# A1-A1_Active_Bias.net
KiCad netlist of a schematic drawn in Altium Designer
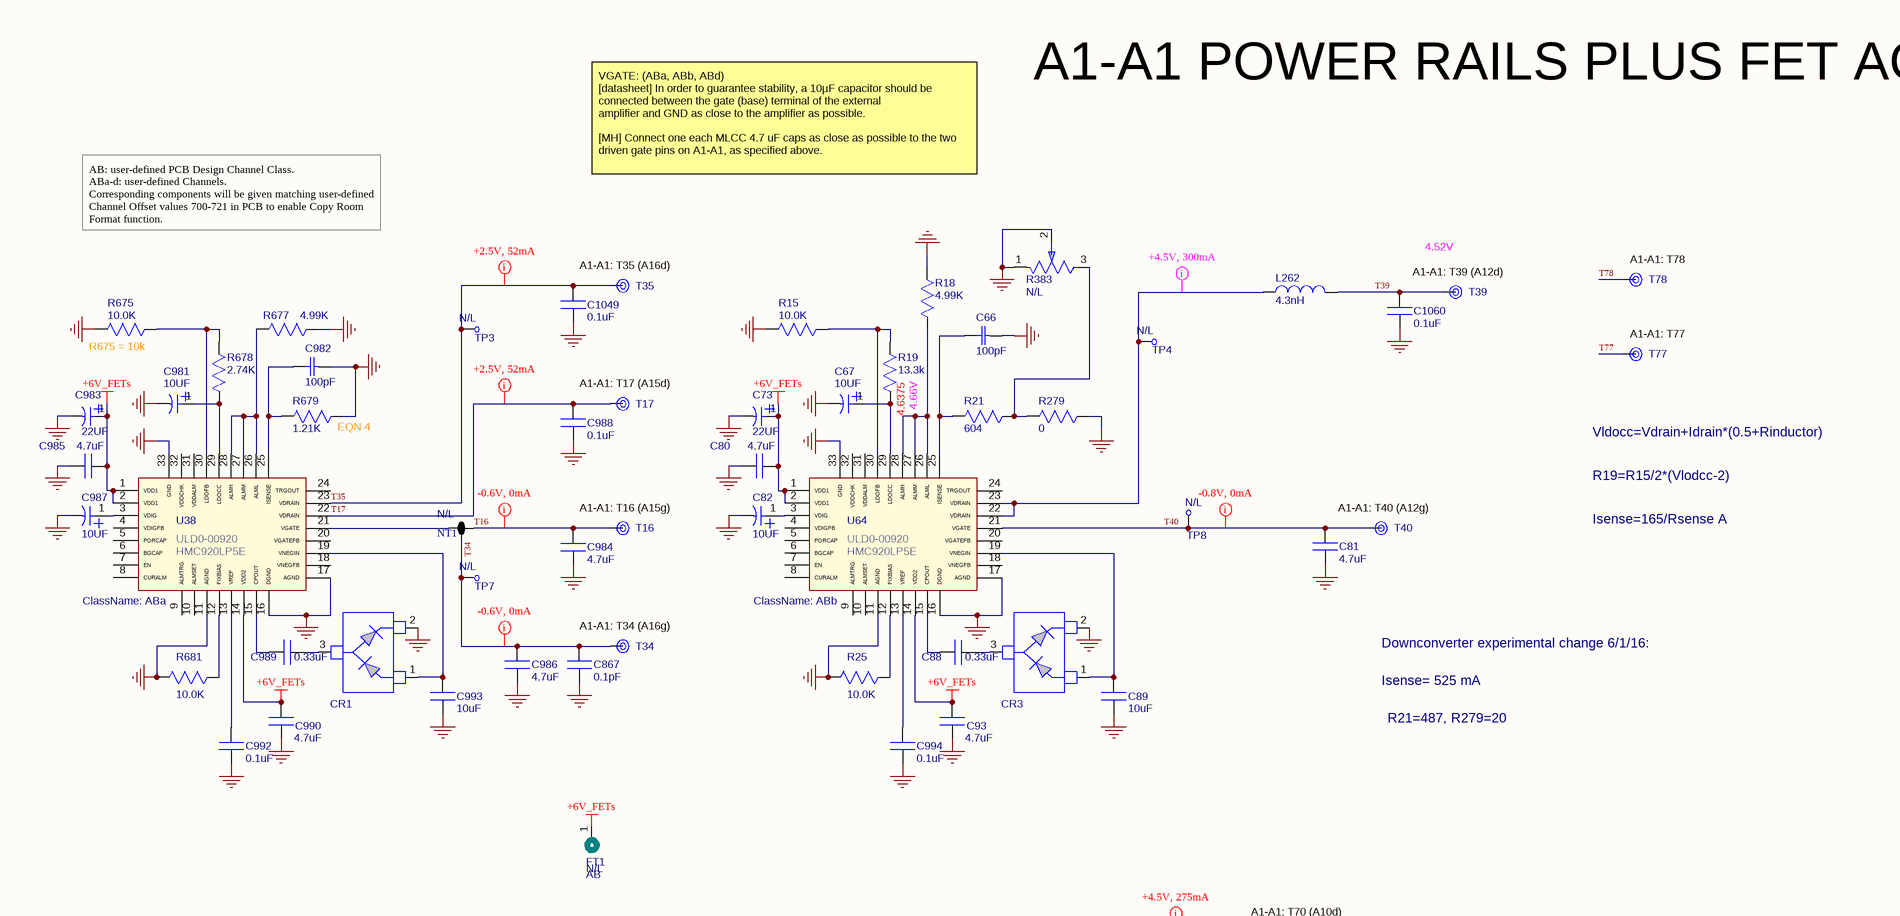
[diagram p0: A1-A1 Active Bias.SchDoc, top left]
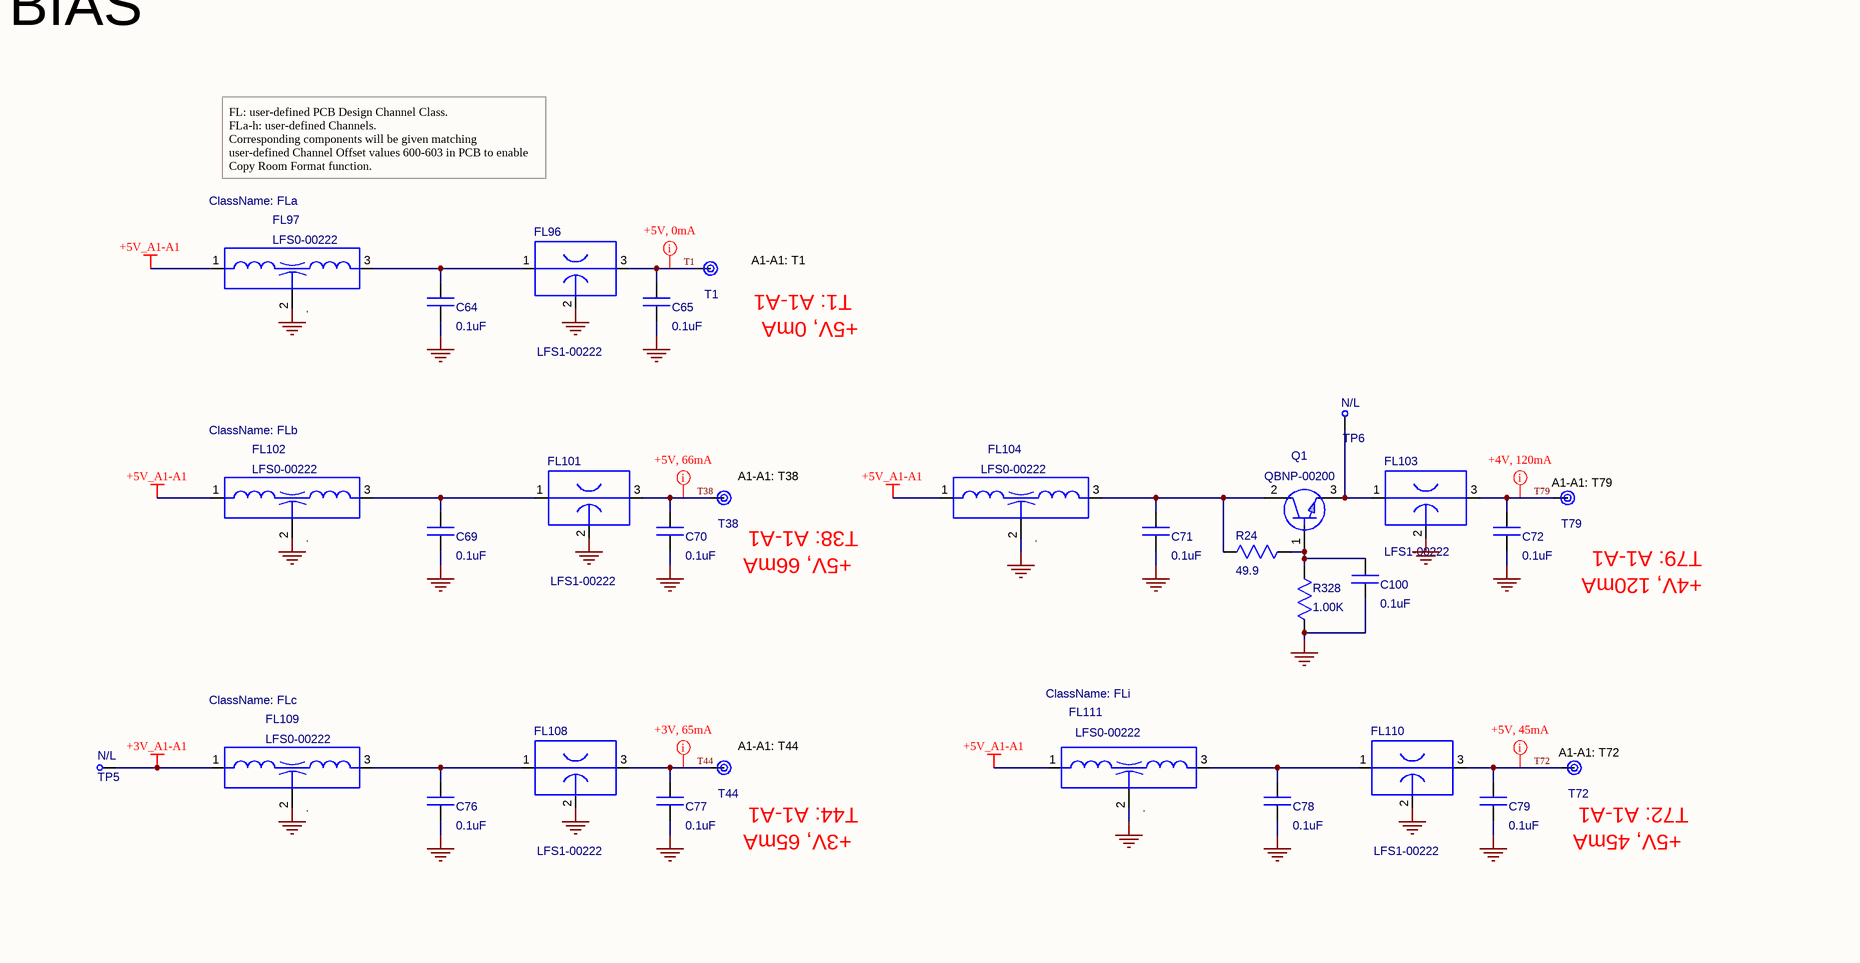
[diagram p1: A1-A1 Active Bias.SchDoc, top right]
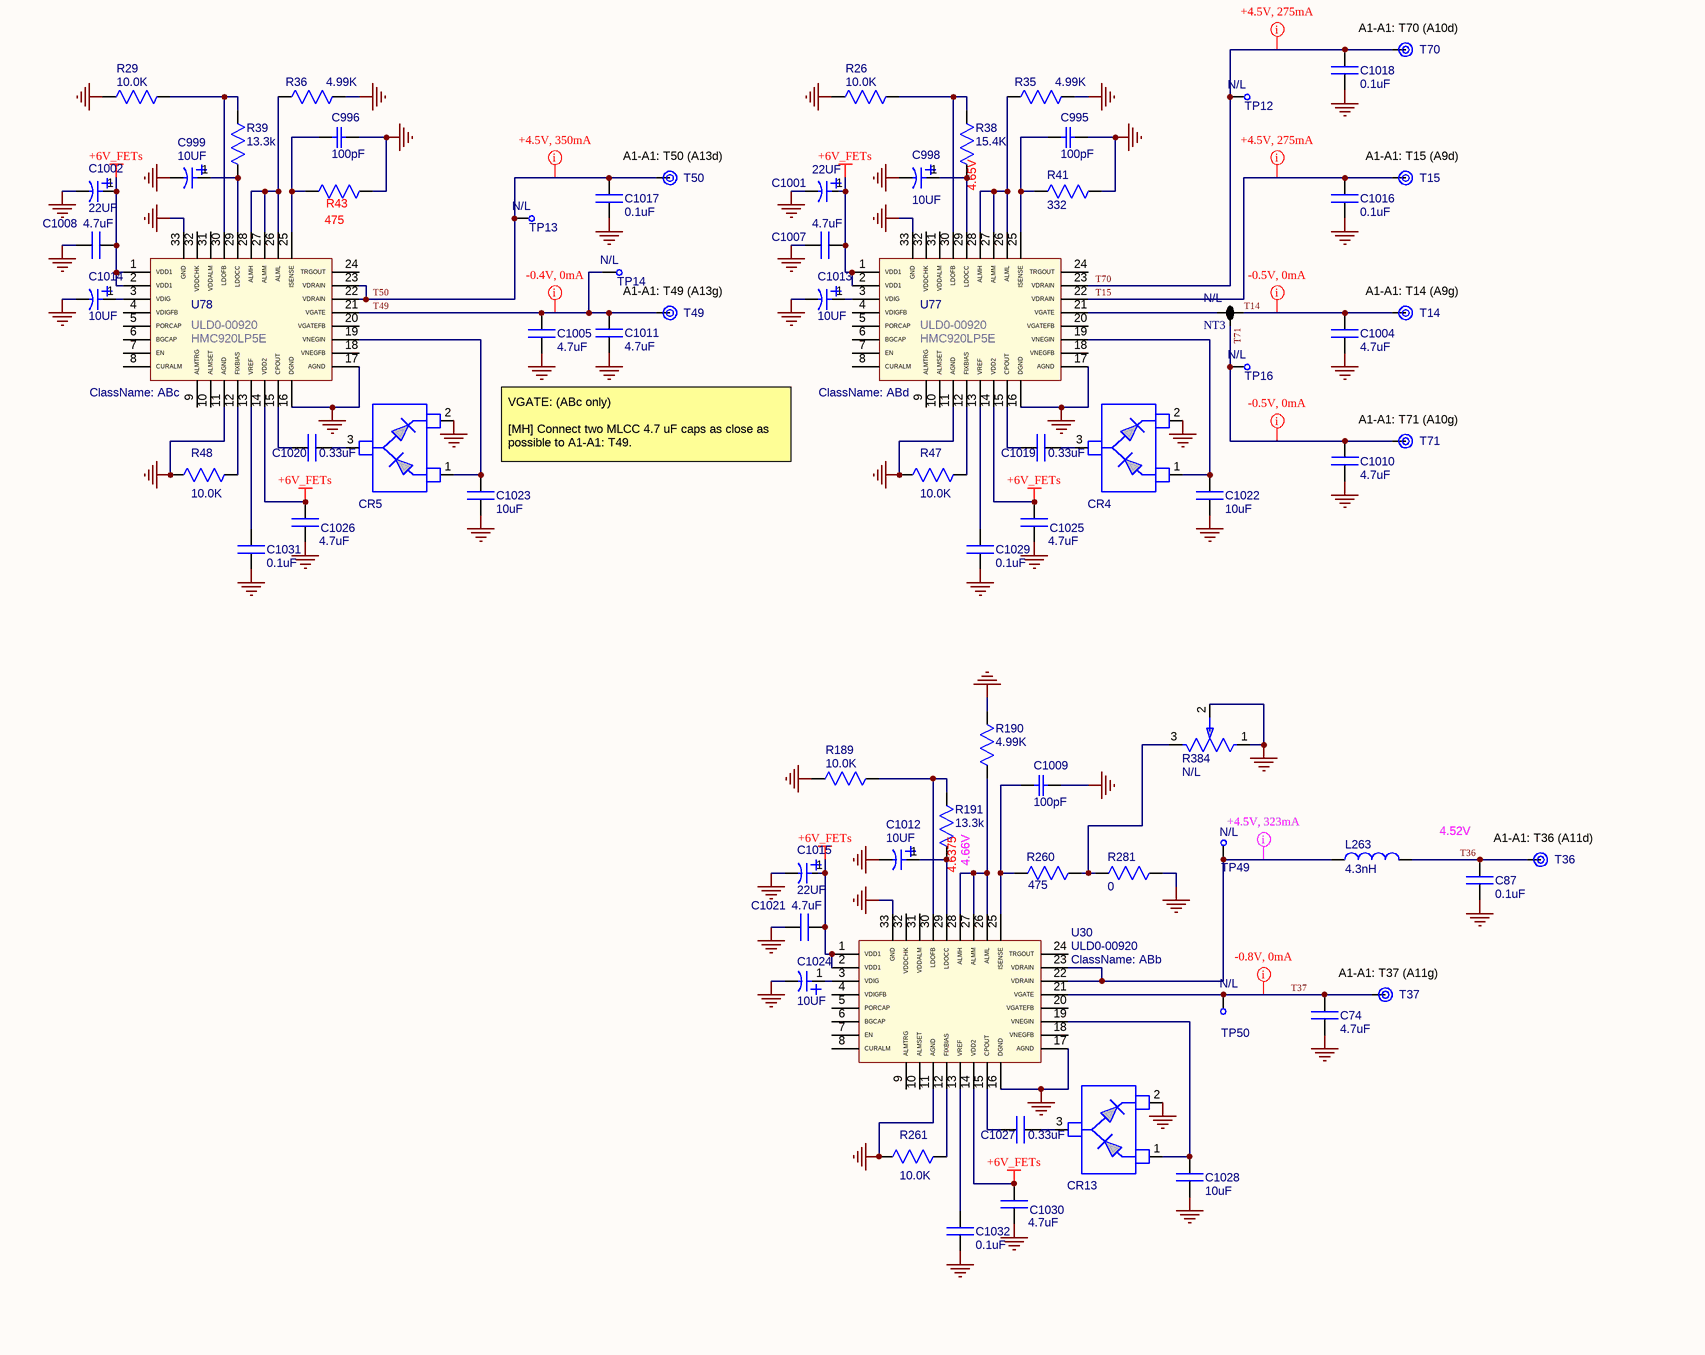
[diagram p2: A1-A1 Active Bias.SchDoc, bottom left]
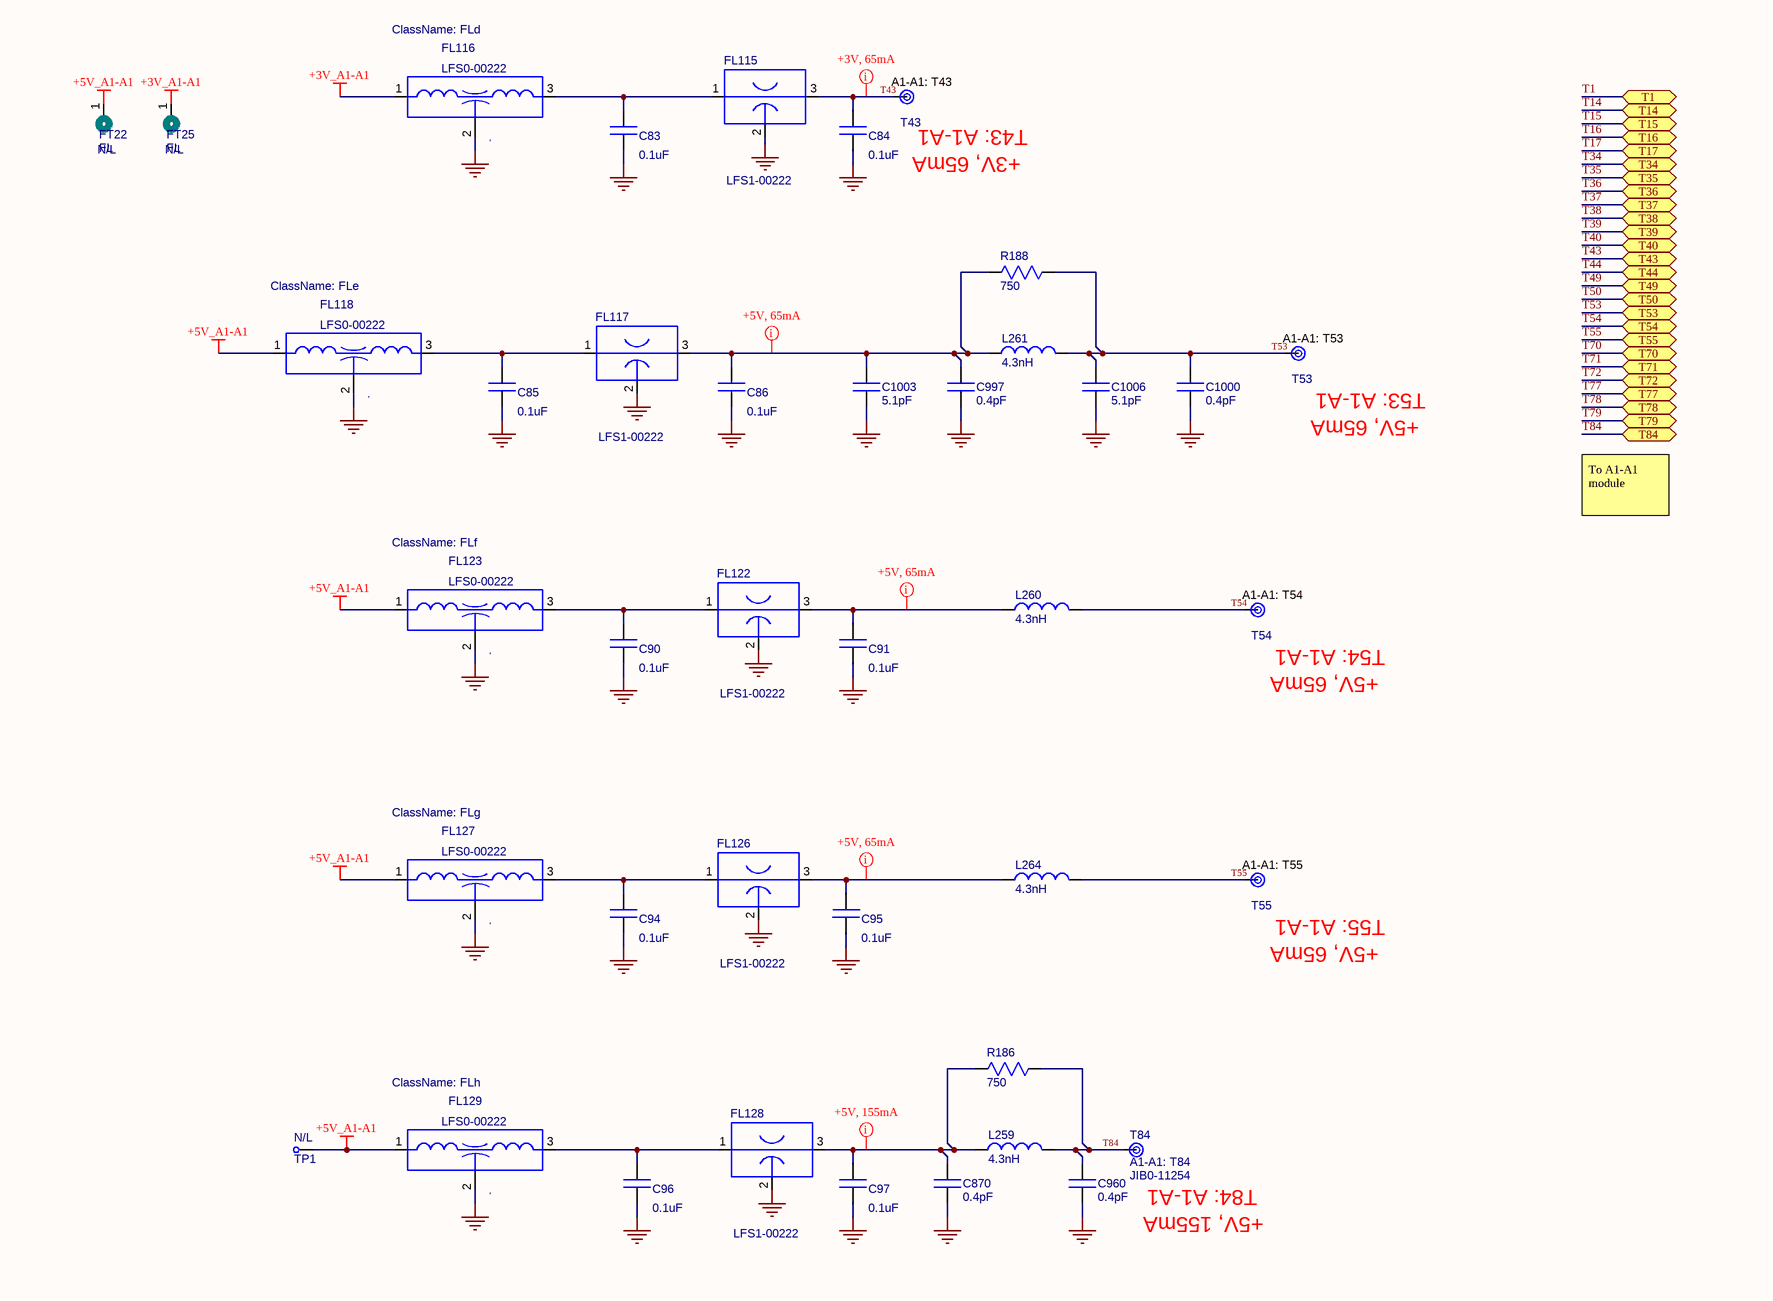
[diagram p3: A1-A1 Active Bias.SchDoc, bottom right]

(export (version "E")
  (design (tool "Eeschema 10.0.6"))
  (components
    (comp (ref "C64")
      (value "0.1uF")
      (footprint "CAP-0603-H035-N")
      (description ".1UF;10%;X7R;16V;CHIP;0603")
      (fields (field (name "APPROVED") "CL"))
      (libsource (lib "Giga-tronics") (part "CK45-04100"))
    )
    (comp (ref "C65")
      (value "0.1uF")
      (footprint "CAP-0603-H035-N")
      (description ".1UF;10%;X7R;16V;CHIP;0603")
      (fields (field (name "APPROVED") "CL"))
      (libsource (lib "Giga-tronics") (part "CK45-04100"))
    )
    (comp (ref "C66")
      (value "100pF")
      (footprint "CC0603-P")
      (description "100 PF;5%;COG;>50V;CHIP;0603; RF footprint")
      (fields (field (name "Comment") "CK45-01100[RF]") (field (name "APPROVED") "NB"))
      (libsource (lib "Giga-tronics") (part "CK45-01100[RF]"))
    )
    (comp (ref "C67")
      (value "10UF")
      (footprint "CAPP-3216-18")
      (description "10 UF;10%;10V;3.4 OHM ESR;3216")
      (fields (field (name "APPROVED") "XiaoXiao"))
      (libsource (lib "Giga-tronics") (part "CT10-S6100"))
    )
    (comp (ref "C69")
      (value "0.1uF")
      (footprint "CAP-0603-H035-N")
      (description ".1UF;10%;X7R;16V;CHIP;0603")
      (fields (field (name "APPROVED") "CL"))
      (libsource (lib "Giga-tronics") (part "CK45-04100"))
    )
    (comp (ref "C70")
      (value "0.1uF")
      (footprint "CAP-0603-H035-N")
      (description ".1UF;10%;X7R;16V;CHIP;0603")
      (fields (field (name "APPROVED") "CL"))
      (libsource (lib "Giga-tronics") (part "CK45-04100"))
    )
    (comp (ref "C71")
      (value "0.1uF")
      (footprint "CAP-0603-H035-N")
      (description ".1UF;10%;X7R;16V;CHIP;0603")
      (fields (field (name "APPROVED") "CL"))
      (libsource (lib "Giga-tronics") (part "CK45-04100"))
    )
    (comp (ref "C72")
      (value "0.1uF")
      (footprint "CAP-0603-H035-N")
      (description ".1UF;10%;X7R;16V;CHIP;0603")
      (fields (field (name "APPROVED") "CL"))
      (libsource (lib "Giga-tronics") (part "CK45-04100"))
    )
    (comp (ref "C73")
      (value "22UF")
      (footprint "CAPP-7343-31-N")
      (description "22UF;10%;20V;EIA 7343;SMT")
      (fields (field (name "APPROVED") "XiaoXiao"))
      (libsource (lib "Giga-tronics") (part "CT20-S6220"))
    )
    (comp (ref "C74")
      (value "4.7uF")
      (footprint "CAP-0402-N")
      (description "4.7 uF,10%;X5R;6.3V,CHIP;0402")
      (libsource (lib "Giga-tronics") (part "CK40-05470"))
    )
    (comp (ref "C76")
      (value "0.1uF")
      (footprint "CAP-0603-H035-N")
      (description ".1UF;10%;X7R;16V;CHIP;0603")
      (fields (field (name "APPROVED") "CL"))
      (libsource (lib "Giga-tronics") (part "CK45-04100"))
    )
    (comp (ref "C77")
      (value "0.1uF")
      (footprint "CAP-0603-H035-N")
      (description ".1UF;10%;X7R;16V;CHIP;0603")
      (fields (field (name "APPROVED") "CL"))
      (libsource (lib "Giga-tronics") (part "CK45-04100"))
    )
    (comp (ref "C78")
      (value "0.1uF")
      (footprint "CAP-0603-H035-N")
      (description ".1UF;10%;X7R;16V;CHIP;0603")
      (fields (field (name "APPROVED") "CL"))
      (libsource (lib "Giga-tronics") (part "CK45-04100"))
    )
    (comp (ref "C79")
      (value "0.1uF")
      (footprint "CAP-0603-H035-N")
      (description ".1UF;10%;X7R;16V;CHIP;0603")
      (fields (field (name "APPROVED") "CL"))
      (libsource (lib "Giga-tronics") (part "CK45-04100"))
    )
    (comp (ref "C80")
      (value "4.7uF")
      (footprint "CAP-0805-N")
      (description "4.7uF 25V X5R CHIP CERAMIC")
      (fields (field (name "APPROVED") "CL"))
      (libsource (lib "Giga-tronics") (part "CK50-15470"))
    )
    (comp (ref "C81")
      (value "4.7uF")
      (footprint "CAP-0402-N")
      (description "4.7 uF,10%;X5R;6.3V,CHIP;0402")
      (libsource (lib "Giga-tronics") (part "CK40-05470"))
    )
    (comp (ref "C82")
      (value "10UF")
      (footprint "CAPP-3216-18")
      (description "10 UF;10%;10V;3.4 OHM ESR;3216")
      (fields (field (name "APPROVED") "XiaoXiao"))
      (libsource (lib "") (part "CT10-S6100_1"))
    )
    (comp (ref "C83")
      (value "0.1uF")
      (footprint "CAP-0603-H035-N")
      (description ".1UF;10%;X7R;16V;CHIP;0603")
      (fields (field (name "APPROVED") "CL"))
      (libsource (lib "Giga-tronics") (part "CK45-04100"))
    )
    (comp (ref "C84")
      (value "0.1uF")
      (footprint "CAP-0603-H035-N")
      (description ".1UF;10%;X7R;16V;CHIP;0603")
      (fields (field (name "APPROVED") "CL"))
      (libsource (lib "Giga-tronics") (part "CK45-04100"))
    )
    (comp (ref "C85")
      (value "0.1uF")
      (footprint "CAP-0603-H035-N")
      (description ".1UF;10%;X7R;16V;CHIP;0603")
      (fields (field (name "APPROVED") "CL"))
      (libsource (lib "Giga-tronics") (part "CK45-04100"))
    )
    (comp (ref "C86")
      (value "0.1uF")
      (footprint "CAP-0603-H035-N")
      (description ".1UF;10%;X7R;16V;CHIP;0603")
      (fields (field (name "APPROVED") "CL"))
      (libsource (lib "Giga-tronics") (part "CK45-04100"))
    )
    (comp (ref "C87")
      (value "0.1uF")
      (footprint "CAP-0603-H035-N")
      (description ".1UF;10%;X7R;16V;CHIP;0603")
      (fields (field (name "APPROVED") "CL"))
      (libsource (lib "Giga-tronics") (part "CK45-04100"))
    )
    (comp (ref "C88")
      (value "0.33uF")
      (footprint "CAP-0805-N")
      (description ".33 UF X7R CHIP CERAMIC")
      (fields (field (name "APPROVED") "CL"))
      (libsource (lib "Giga-tronics") (part "CK50-04330"))
    )
    (comp (ref "C89")
      (value "10uF")
      (footprint "CAP-0805-N")
      (description "10uF 16V X5R CHIP CERAMIC")
      (fields (field (name "APPROVED") "CL"))
      (libsource (lib "Giga-tronics") (part "CK50-06100"))
    )
    (comp (ref "C90")
      (value "0.1uF")
      (footprint "CAP-0603-H035-N")
      (description ".1UF;10%;X7R;16V;CHIP;0603")
      (fields (field (name "APPROVED") "CL"))
      (libsource (lib "Giga-tronics") (part "CK45-04100"))
    )
    (comp (ref "C91")
      (value "0.1uF")
      (footprint "CAP-0603-H035-N")
      (description ".1UF;10%;X7R;16V;CHIP;0603")
      (fields (field (name "APPROVED") "CL"))
      (libsource (lib "Giga-tronics") (part "CK45-04100"))
    )
    (comp (ref "C93")
      (value "4.7uF")
      (footprint "CAP-0805-N")
      (description "4.7uF 25V X5R CHIP CERAMIC")
      (fields (field (name "APPROVED") "CL"))
      (libsource (lib "Giga-tronics") (part "CK50-15470"))
    )
    (comp (ref "C94")
      (value "0.1uF")
      (footprint "CAP-0603-H035-N")
      (description ".1UF;10%;X7R;16V;CHIP;0603")
      (fields (field (name "APPROVED") "CL"))
      (libsource (lib "Giga-tronics") (part "CK45-04100"))
    )
    (comp (ref "C95")
      (value "0.1uF")
      (footprint "CAP-0603-H035-N")
      (description ".1UF;10%;X7R;16V;CHIP;0603")
      (fields (field (name "APPROVED") "CL"))
      (libsource (lib "Giga-tronics") (part "CK45-04100"))
    )
    (comp (ref "C96")
      (value "0.1uF")
      (footprint "CAP-0603-H035-N")
      (description ".1UF;10%;X7R;16V;CHIP;0603")
      (fields (field (name "APPROVED") "CL"))
      (libsource (lib "Giga-tronics") (part "CK45-04100"))
    )
    (comp (ref "C97")
      (value "0.1uF")
      (footprint "CAP-0603-H035-N")
      (description ".1UF;10%;X7R;16V;CHIP;0603")
      (fields (field (name "APPROVED") "CL"))
      (libsource (lib "Giga-tronics") (part "CK45-04100"))
    )
    (comp (ref "C100")
      (value "0.1uF")
      (footprint "CAP-0603-H035-N")
      (description ".1UF;10%;X7R;16V;CHIP;0603")
      (fields (field (name "APPROVED") "CL"))
      (libsource (lib "Giga-tronics") (part "CK45-04100"))
    )
    (comp (ref "C867")
      (value "0.1pF")
      (footprint "CAP-0402-N")
      (description ".1 PF;200V;.05PF;HIGH Q;SMT;CERAMIC;0402")
      (fields (field (name "APPROVED") "CL"))
      (libsource (lib "Giga-tronics") (part "CK41-00001"))
    )
    (comp (ref "C870")
      (value "0.4pF")
      (footprint "CAP-0402-RF")
      (description ".4 PF;200V;.05PF;HIGH Q;SMT;CERAMIC;0402")
      (fields (field (name "APPROVED") "CL"))
      (libsource (lib "Giga-tronics") (part "CK41-00004"))
    )
    (comp (ref "C960")
      (value "0.4pF")
      (footprint "CAP-0402-RF")
      (description ".4 PF;200V;.05PF;HIGH Q;SMT;CERAMIC;0402")
      (fields (field (name "APPROVED") "CL"))
      (libsource (lib "Giga-tronics") (part "CK41-00004"))
    )
    (comp (ref "C981")
      (value "10UF")
      (footprint "CAPP-3216-18")
      (description "10 UF;10%;10V;3.4 OHM ESR;3216")
      (fields (field (name "APPROVED") "XiaoXiao"))
      (libsource (lib "Giga-tronics") (part "CT10-S6100"))
    )
    (comp (ref "C982")
      (value "100pF")
      (footprint "CC0603-P")
      (description "100 PF;5%;COG;>50V;CHIP;0603; RF footprint")
      (fields (field (name "Comment") "CK45-01100[RF]") (field (name "APPROVED") "NB"))
      (libsource (lib "Giga-tronics") (part "CK45-01100[RF]"))
    )
    (comp (ref "C983")
      (value "22UF")
      (footprint "CAPP-7343-31-N")
      (description "22UF;10%;20V;EIA 7343;SMT")
      (fields (field (name "APPROVED") "XiaoXiao"))
      (libsource (lib "Giga-tronics") (part "CT20-S6220"))
    )
    (comp (ref "C984")
      (value "4.7uF")
      (footprint "CAP-0402-N")
      (description "4.7 uF,10%;X5R;6.3V,CHIP;0402")
      (libsource (lib "Giga-tronics") (part "CK40-05470"))
    )
    (comp (ref "C985")
      (value "4.7uF")
      (footprint "CAP-0805-N")
      (description "4.7uF 25V X5R CHIP CERAMIC")
      (fields (field (name "APPROVED") "CL"))
      (libsource (lib "Giga-tronics") (part "CK50-15470"))
    )
    (comp (ref "C986")
      (value "4.7uF")
      (footprint "CAP-0402-N")
      (description "4.7 uF,10%;X5R;6.3V,CHIP;0402")
      (libsource (lib "Giga-tronics") (part "CK40-05470"))
    )
    (comp (ref "C987")
      (value "10UF")
      (footprint "CAPP-3216-18")
      (description "10 UF;10%;10V;3.4 OHM ESR;3216")
      (fields (field (name "APPROVED") "XiaoXiao"))
      (libsource (lib "") (part "CT10-S6100_1"))
    )
    (comp (ref "C988")
      (value "0.1uF")
      (footprint "CAP-0603-H035-N")
      (description ".1UF;10%;X7R;16V;CHIP;0603")
      (fields (field (name "APPROVED") "CL"))
      (libsource (lib "Giga-tronics") (part "CK45-04100"))
    )
    (comp (ref "C989")
      (value "0.33uF")
      (footprint "CAP-0805-N")
      (description ".33 UF X7R CHIP CERAMIC")
      (fields (field (name "APPROVED") "CL"))
      (libsource (lib "Giga-tronics") (part "CK50-04330"))
    )
    (comp (ref "C990")
      (value "4.7uF")
      (footprint "CAP-0805-N")
      (description "4.7uF 25V X5R CHIP CERAMIC")
      (fields (field (name "APPROVED") "CL"))
      (libsource (lib "Giga-tronics") (part "CK50-15470"))
    )
    (comp (ref "C992")
      (value "0.1uF")
      (footprint "CAP-0603-H035-N")
      (description ".1UF;10%;X7R;16V;CHIP;0603")
      (fields (field (name "APPROVED") "CL"))
      (libsource (lib "Giga-tronics") (part "CK45-04100"))
    )
    (comp (ref "C993")
      (value "10uF")
      (footprint "CAP-0805-N")
      (description "10uF 16V X5R CHIP CERAMIC")
      (fields (field (name "APPROVED") "CL"))
      (libsource (lib "Giga-tronics") (part "CK50-06100"))
    )
    (comp (ref "C994")
      (value "0.1uF")
      (footprint "CAP-0603-H035-N")
      (description ".1UF;10%;X7R;16V;CHIP;0603")
      (fields (field (name "APPROVED") "CL"))
      (libsource (lib "Giga-tronics") (part "CK45-04100"))
    )
    (comp (ref "C995")
      (value "100pF")
      (footprint "CC0603-P")
      (description "100 PF;5%;COG;>50V;CHIP;0603; RF footprint")
      (fields (field (name "Comment") "CK45-01100[RF]") (field (name "APPROVED") "NB"))
      (libsource (lib "Giga-tronics") (part "CK45-01100[RF]"))
    )
    (comp (ref "C996")
      (value "100pF")
      (footprint "CC0603-P")
      (description "100 PF;5%;COG;>50V;CHIP;0603; RF footprint")
      (fields (field (name "Comment") "CK45-01100[RF]") (field (name "APPROVED") "NB"))
      (libsource (lib "Giga-tronics") (part "CK45-01100[RF]"))
    )
    (comp (ref "C997")
      (value "0.4pF")
      (footprint "CAP-0402-RF")
      (description ".4 PF;200V;.05PF;HIGH Q;SMT;CERAMIC;0402")
      (fields (field (name "APPROVED") "CL"))
      (libsource (lib "Giga-tronics") (part "CK41-00004"))
    )
    (comp (ref "C998")
      (value "10UF")
      (footprint "CAPP-3216-18")
      (description "10 UF;10%;10V;3.4 OHM ESR;3216")
      (fields (field (name "APPROVED") "XiaoXiao"))
      (libsource (lib "Giga-tronics") (part "CT10-S6100"))
    )
    (comp (ref "C999")
      (value "10UF")
      (footprint "CAPP-3216-18")
      (description "10 UF;10%;10V;3.4 OHM ESR;3216")
      (fields (field (name "APPROVED") "XiaoXiao"))
      (libsource (lib "Giga-tronics") (part "CT10-S6100"))
    )
    (comp (ref "C1000")
      (value "0.4pF")
      (footprint "CAP-0402-RF")
      (description ".4 PF;200V;.05PF;HIGH Q;SMT;CERAMIC;0402")
      (fields (field (name "APPROVED") "CL"))
      (libsource (lib "Giga-tronics") (part "CK41-00004"))
    )
    (comp (ref "C1001")
      (value "22UF")
      (footprint "CAPP-7343-31-N")
      (description "22UF;10%;20V;EIA 7343;SMT")
      (fields (field (name "APPROVED") "XiaoXiao"))
      (libsource (lib "Giga-tronics") (part "CT20-S6220"))
    )
    (comp (ref "C1002")
      (value "22UF")
      (footprint "CAPP-7343-31-N")
      (description "22UF;10%;20V;EIA 7343;SMT")
      (fields (field (name "APPROVED") "XiaoXiao"))
      (libsource (lib "Giga-tronics") (part "CT20-S6220"))
    )
    (comp (ref "C1003")
      (value "5.1pF")
      (footprint "CAP-0402-RF")
      (description "5.1 PF;200V;.1PF;HIGH Q;SMT;CERAMIC;0402")
      (fields (field (name "APPROVED") "CL"))
      (libsource (lib "Giga-tronics") (part "CK41-00051"))
    )
    (comp (ref "C1004")
      (value "4.7uF")
      (footprint "CAP-0402-N")
      (description "4.7 uF,10%;X5R;6.3V,CHIP;0402")
      (libsource (lib "Giga-tronics") (part "CK40-05470"))
    )
    (comp (ref "C1005")
      (value "4.7uF")
      (footprint "CAP-0402-N")
      (description "4.7 uF,10%;X5R;6.3V,CHIP;0402")
      (libsource (lib "Giga-tronics") (part "CK40-05470"))
    )
    (comp (ref "C1006")
      (value "5.1pF")
      (footprint "CAP-0402-RF")
      (description "5.1 PF;200V;.1PF;HIGH Q;SMT;CERAMIC;0402")
      (fields (field (name "APPROVED") "CL"))
      (libsource (lib "Giga-tronics") (part "CK41-00051"))
    )
    (comp (ref "C1007")
      (value "4.7uF")
      (footprint "CAP-0805-N")
      (description "4.7uF 25V X5R CHIP CERAMIC")
      (fields (field (name "APPROVED") "CL"))
      (libsource (lib "Giga-tronics") (part "CK50-15470"))
    )
    (comp (ref "C1008")
      (value "4.7uF")
      (footprint "CAP-0805-N")
      (description "4.7uF 25V X5R CHIP CERAMIC")
      (fields (field (name "APPROVED") "CL"))
      (libsource (lib "Giga-tronics") (part "CK50-15470"))
    )
    (comp (ref "C1009")
      (value "100pF")
      (footprint "CC0603-P")
      (description "100 PF;5%;COG;>50V;CHIP;0603; RF footprint")
      (fields (field (name "Comment") "CK45-01100[RF]") (field (name "APPROVED") "NB"))
      (libsource (lib "Giga-tronics") (part "CK45-01100[RF]"))
    )
    (comp (ref "C1010")
      (value "4.7uF")
      (footprint "CAP-0402-N")
      (description "4.7 uF,10%;X5R;6.3V,CHIP;0402")
      (libsource (lib "Giga-tronics") (part "CK40-05470"))
    )
    (comp (ref "C1011")
      (value "4.7uF")
      (footprint "CAP-0402-N")
      (description "4.7 uF,10%;X5R;6.3V,CHIP;0402")
      (libsource (lib "Giga-tronics") (part "CK40-05470"))
    )
    (comp (ref "C1012")
      (value "10UF")
      (footprint "CAPP-3216-18")
      (description "10 UF;10%;10V;3.4 OHM ESR;3216")
      (fields (field (name "APPROVED") "XiaoXiao"))
      (libsource (lib "Giga-tronics") (part "CT10-S6100"))
    )
    (comp (ref "C1013")
      (value "10UF")
      (footprint "CAPP-3216-18")
      (description "10 UF;10%;10V;3.4 OHM ESR;3216")
      (fields (field (name "APPROVED") "XiaoXiao"))
      (libsource (lib "Giga-tronics") (part "CT10-S6100"))
    )
    (comp (ref "C1014")
      (value "10UF")
      (footprint "CAPP-3216-18")
      (description "10 UF;10%;10V;3.4 OHM ESR;3216")
      (fields (field (name "APPROVED") "XiaoXiao"))
      (libsource (lib "Giga-tronics") (part "CT10-S6100"))
    )
    (comp (ref "C1015")
      (value "22UF")
      (footprint "CAPP-7343-31-N")
      (description "22UF;10%;20V;EIA 7343;SMT")
      (fields (field (name "APPROVED") "XiaoXiao"))
      (libsource (lib "Giga-tronics") (part "CT20-S6220"))
    )
    (comp (ref "C1016")
      (value "0.1uF")
      (footprint "CAP-0603-H035-N")
      (description ".1UF;10%;X7R;16V;CHIP;0603")
      (fields (field (name "APPROVED") "CL"))
      (libsource (lib "Giga-tronics") (part "CK45-04100"))
    )
    (comp (ref "C1017")
      (value "0.1uF")
      (footprint "CAP-0603-H035-N")
      (description ".1UF;10%;X7R;16V;CHIP;0603")
      (fields (field (name "APPROVED") "CL"))
      (libsource (lib "Giga-tronics") (part "CK45-04100"))
    )
    (comp (ref "C1018")
      (value "0.1uF")
      (footprint "CAP-0603-H035-N")
      (description ".1UF;10%;X7R;16V;CHIP;0603")
      (fields (field (name "APPROVED") "CL"))
      (libsource (lib "Giga-tronics") (part "CK45-04100"))
    )
    (comp (ref "C1019")
      (value "0.33uF")
      (footprint "CAP-0805-N")
      (description ".33 UF X7R CHIP CERAMIC")
      (fields (field (name "APPROVED") "CL"))
      (libsource (lib "Giga-tronics") (part "CK50-04330"))
    )
    (comp (ref "C1020")
      (value "0.33uF")
      (footprint "CAP-0805-N")
      (description ".33 UF X7R CHIP CERAMIC")
      (fields (field (name "APPROVED") "CL"))
      (libsource (lib "Giga-tronics") (part "CK50-04330"))
    )
    (comp (ref "C1021")
      (value "4.7uF")
      (footprint "CAP-0805-N")
      (description "4.7uF 25V X5R CHIP CERAMIC")
      (fields (field (name "APPROVED") "CL"))
      (libsource (lib "Giga-tronics") (part "CK50-15470"))
    )
    (comp (ref "C1022")
      (value "10uF")
      (footprint "CAP-0805-N")
      (description "10uF 16V X5R CHIP CERAMIC")
      (fields (field (name "APPROVED") "CL"))
      (libsource (lib "Giga-tronics") (part "CK50-06100"))
    )
    (comp (ref "C1023")
      (value "10uF")
      (footprint "CAP-0805-N")
      (description "10uF 16V X5R CHIP CERAMIC")
      (fields (field (name "APPROVED") "CL"))
      (libsource (lib "Giga-tronics") (part "CK50-06100"))
    )
    (comp (ref "C1024")
      (value "10UF")
      (footprint "CAPP-3216-18")
      (description "10 UF;10%;10V;3.4 OHM ESR;3216")
      (fields (field (name "APPROVED") "XiaoXiao"))
      (libsource (lib "") (part "CT10-S6100_1"))
    )
    (comp (ref "C1025")
      (value "4.7uF")
      (footprint "CAP-0805-N")
      (description "4.7uF 25V X5R CHIP CERAMIC")
      (fields (field (name "APPROVED") "CL"))
      (libsource (lib "Giga-tronics") (part "CK50-15470"))
    )
    (comp (ref "C1026")
      (value "4.7uF")
      (footprint "CAP-0805-N")
      (description "4.7uF 25V X5R CHIP CERAMIC")
      (fields (field (name "APPROVED") "CL"))
      (libsource (lib "Giga-tronics") (part "CK50-15470"))
    )
    (comp (ref "C1027")
      (value "0.33uF")
      (footprint "CAP-0805-N")
      (description ".33 UF X7R CHIP CERAMIC")
      (fields (field (name "APPROVED") "CL"))
      (libsource (lib "Giga-tronics") (part "CK50-04330"))
    )
    (comp (ref "C1028")
      (value "10uF")
      (footprint "CAP-0805-N")
      (description "10uF 16V X5R CHIP CERAMIC")
      (fields (field (name "APPROVED") "CL"))
      (libsource (lib "Giga-tronics") (part "CK50-06100"))
    )
    (comp (ref "C1029")
      (value "0.1uF")
      (footprint "CAP-0603-H035-N")
      (description ".1UF;10%;X7R;16V;CHIP;0603")
      (fields (field (name "APPROVED") "CL"))
      (libsource (lib "Giga-tronics") (part "CK45-04100"))
    )
    (comp (ref "C1030")
      (value "4.7uF")
      (footprint "CAP-0805-N")
      (description "4.7uF 25V X5R CHIP CERAMIC")
      (fields (field (name "APPROVED") "CL"))
      (libsource (lib "Giga-tronics") (part "CK50-15470"))
    )
    (comp (ref "C1031")
      (value "0.1uF")
      (footprint "CAP-0603-H035-N")
      (description ".1UF;10%;X7R;16V;CHIP;0603")
      (fields (field (name "APPROVED") "CL"))
      (libsource (lib "Giga-tronics") (part "CK45-04100"))
    )
    (comp (ref "C1032")
      (value "0.1uF")
      (footprint "CAP-0603-H035-N")
      (description ".1UF;10%;X7R;16V;CHIP;0603")
      (fields (field (name "APPROVED") "CL"))
      (libsource (lib "Giga-tronics") (part "CK45-04100"))
    )
    (comp (ref "C1049")
      (value "0.1uF")
      (footprint "CAP-0603-H035-N")
      (description ".1UF;10%;X7R;16V;CHIP;0603")
      (fields (field (name "APPROVED") "CL"))
      (libsource (lib "Giga-tronics") (part "CK45-04100"))
    )
    (comp (ref "C1060")
      (value "0.1uF")
      (footprint "CAP-0603-H035-N")
      (description ".1UF;10%;X7R;16V;CHIP;0603")
      (fields (field (name "APPROVED") "CL"))
      (libsource (lib "Giga-tronics") (part "CK45-04100"))
    )
    (comp (ref "CR1")
      (value "Diode;Dual;Schottky;.4VF@10MA;5NS;SOT23")
      (footprint "SOT23-N")
      (fields (field (name "APPROVED") "CL"))
      (libsource (lib "Giga-tronics") (part "DSA2-00054"))
    )
    (comp (ref "CR3")
      (value "Diode;Dual;Schottky;.4VF@10MA;5NS;SOT23")
      (footprint "SOT23-N")
      (fields (field (name "APPROVED") "CL"))
      (libsource (lib "Giga-tronics") (part "DSA2-00054"))
    )
    (comp (ref "CR4")
      (value "Diode;Dual;Schottky;.4VF@10MA;5NS;SOT23")
      (footprint "SOT23-N")
      (fields (field (name "APPROVED") "CL"))
      (libsource (lib "Giga-tronics") (part "DSA2-00054"))
    )
    (comp (ref "CR5")
      (value "Diode;Dual;Schottky;.4VF@10MA;5NS;SOT23")
      (footprint "SOT23-N")
      (fields (field (name "APPROVED") "CL"))
      (libsource (lib "Giga-tronics") (part "DSA2-00054"))
    )
    (comp (ref "CR13")
      (value "Diode;Dual;Schottky;.4VF@10MA;5NS;SOT23")
      (footprint "SOT23-N")
      (fields (field (name "APPROVED") "CL"))
      (libsource (lib "Giga-tronics") (part "DSA2-00054"))
    )
    (comp (ref "FL96")
      (value "NFM18CC222R1C3")
      (footprint "FIL-NFL18C")
      (description "2200 PF FEED THRU FILTER 0603")
      (fields (field (name "G_PN") "LFS1-00222") (field (name "APPROVED") "NM"))
      (libsource (lib "Giga-tronics") (part "LFS1-00222"))
    )
    (comp (ref "FL97")
      (value "Filter EMI 2200PF,1206")
      (footprint "FIL-NFE31P-1206-4P")
      (fields
        (field (name "G_PN") "LFS0-00222")
        (field (name "CLASSNAME") "FLa")
        (field (name "APPROVED") "CL")
      )
      (libsource (lib "Giga-tronics") (part "LFS0-00222"))
    )
    (comp (ref "FL101")
      (value "NFM18CC222R1C3")
      (footprint "FIL-NFL18C")
      (description "2200 PF FEED THRU FILTER 0603")
      (fields (field (name "G_PN") "LFS1-00222") (field (name "APPROVED") "NM"))
      (libsource (lib "Giga-tronics") (part "LFS1-00222"))
    )
    (comp (ref "FL102")
      (value "Filter EMI 2200PF,1206")
      (footprint "FIL-NFE31P-1206-4P")
      (fields
        (field (name "G_PN") "LFS0-00222")
        (field (name "CLASSNAME") "FLb")
        (field (name "APPROVED") "CL")
      )
      (libsource (lib "Giga-tronics") (part "LFS0-00222"))
    )
    (comp (ref "FL103")
      (value "NFM18CC222R1C3")
      (footprint "FIL-NFL18C")
      (description "2200 PF FEED THRU FILTER 0603")
      (fields (field (name "G_PN") "LFS1-00222") (field (name "APPROVED") "NM"))
      (libsource (lib "Giga-tronics") (part "LFS1-00222"))
    )
    (comp (ref "FL104")
      (value "Filter EMI 2200PF,1206")
      (footprint "FIL-NFE31P-1206-4P")
      (fields (field (name "G_PN") "LFS0-00222") (field (name "APPROVED") "CL"))
      (libsource (lib "Giga-tronics") (part "LFS0-00222"))
    )
    (comp (ref "FL108")
      (value "NFM18CC222R1C3")
      (footprint "FIL-NFL18C")
      (description "2200 PF FEED THRU FILTER 0603")
      (fields (field (name "G_PN") "LFS1-00222") (field (name "APPROVED") "NM"))
      (libsource (lib "Giga-tronics") (part "LFS1-00222"))
    )
    (comp (ref "FL109")
      (value "Filter EMI 2200PF,1206")
      (footprint "FIL-NFE31P-1206-4P")
      (fields
        (field (name "G_PN") "LFS0-00222")
        (field (name "CLASSNAME") "FLc")
        (field (name "APPROVED") "CL")
      )
      (libsource (lib "Giga-tronics") (part "LFS0-00222"))
    )
    (comp (ref "FL110")
      (value "NFM18CC222R1C3")
      (footprint "FIL-NFL18C")
      (description "2200 PF FEED THRU FILTER 0603")
      (fields (field (name "G_PN") "LFS1-00222") (field (name "APPROVED") "NM"))
      (libsource (lib "Giga-tronics") (part "LFS1-00222"))
    )
    (comp (ref "FL111")
      (value "Filter EMI 2200PF,1206")
      (footprint "FIL-NFE31P-1206-4P")
      (fields
        (field (name "G_PN") "LFS0-00222")
        (field (name "CLASSNAME") "FLi")
        (field (name "APPROVED") "CL")
      )
      (libsource (lib "Giga-tronics") (part "LFS0-00222"))
    )
    (comp (ref "FL115")
      (value "NFM18CC222R1C3")
      (footprint "FIL-NFL18C")
      (description "2200 PF FEED THRU FILTER 0603")
      (fields (field (name "G_PN") "LFS1-00222") (field (name "APPROVED") "NM"))
      (libsource (lib "Giga-tronics") (part "LFS1-00222"))
    )
    (comp (ref "FL116")
      (value "Filter EMI 2200PF,1206")
      (footprint "FIL-NFE31P-1206-4P")
      (fields
        (field (name "G_PN") "LFS0-00222")
        (field (name "CLASSNAME") "FLd")
        (field (name "APPROVED") "CL")
      )
      (libsource (lib "Giga-tronics") (part "LFS0-00222"))
    )
    (comp (ref "FL117")
      (value "NFM18CC222R1C3")
      (footprint "FIL-NFL18C")
      (description "2200 PF FEED THRU FILTER 0603")
      (fields (field (name "G_PN") "LFS1-00222") (field (name "APPROVED") "NM"))
      (libsource (lib "Giga-tronics") (part "LFS1-00222"))
    )
    (comp (ref "FL118")
      (value "Filter EMI 2200PF,1206")
      (footprint "FIL-NFE31P-1206-4P")
      (fields
        (field (name "G_PN") "LFS0-00222")
        (field (name "CLASSNAME") "FLe")
        (field (name "APPROVED") "CL")
      )
      (libsource (lib "Giga-tronics") (part "LFS0-00222"))
    )
    (comp (ref "FL122")
      (value "NFM18CC222R1C3")
      (footprint "FIL-NFL18C")
      (description "2200 PF FEED THRU FILTER 0603")
      (fields (field (name "G_PN") "LFS1-00222") (field (name "APPROVED") "NM"))
      (libsource (lib "Giga-tronics") (part "LFS1-00222"))
    )
    (comp (ref "FL123")
      (value "Filter EMI 2200PF,1206")
      (footprint "FIL-NFE31P-1206-4P")
      (fields
        (field (name "G_PN") "LFS0-00222")
        (field (name "CLASSNAME") "FLf")
        (field (name "APPROVED") "CL")
      )
      (libsource (lib "Giga-tronics") (part "LFS0-00222"))
    )
    (comp (ref "FL126")
      (value "NFM18CC222R1C3")
      (footprint "FIL-NFL18C")
      (description "2200 PF FEED THRU FILTER 0603")
      (fields (field (name "G_PN") "LFS1-00222") (field (name "APPROVED") "NM"))
      (libsource (lib "Giga-tronics") (part "LFS1-00222"))
    )
    (comp (ref "FL127")
      (value "Filter EMI 2200PF,1206")
      (footprint "FIL-NFE31P-1206-4P")
      (fields
        (field (name "G_PN") "LFS0-00222")
        (field (name "CLASSNAME") "FLg")
        (field (name "APPROVED") "CL")
      )
      (libsource (lib "Giga-tronics") (part "LFS0-00222"))
    )
    (comp (ref "FL128")
      (value "NFM18CC222R1C3")
      (footprint "FIL-NFL18C")
      (description "2200 PF FEED THRU FILTER 0603")
      (fields (field (name "G_PN") "LFS1-00222") (field (name "APPROVED") "NM"))
      (libsource (lib "Giga-tronics") (part "LFS1-00222"))
    )
    (comp (ref "FL129")
      (value "Filter EMI 2200PF,1206")
      (footprint "FIL-NFE31P-1206-4P")
      (fields
        (field (name "G_PN") "LFS0-00222")
        (field (name "CLASSNAME") "FLh")
        (field (name "APPROVED") "CL")
      )
      (libsource (lib "Giga-tronics") (part "LFS0-00222"))
    )
    (comp (ref "FT1")
      (value "AB")
      (footprint "FromToNode_ML2")
      (fields (field (name "NOLOAD") "N/L") (field (name "APPROVED") "*"))
      (libsource (lib "Giga-tronics") (part "FromToNode"))
    )
    (comp (ref "FT22")
      (value "FL")
      (footprint "FromToNode_ML2")
      (fields (field (name "NOLOAD") "N/L") (field (name "APPROVED") "*"))
      (libsource (lib "Giga-tronics") (part "FromToNode"))
    )
    (comp (ref "FT25")
      (value "FL")
      (footprint "FromToNode_ML2")
      (fields (field (name "NOLOAD") "N/L") (field (name "APPROVED") "*"))
      (libsource (lib "Giga-tronics") (part "FromToNode"))
    )
    (comp (ref "L259")
      (value "4.3nH")
      (footprint "IND-0402HP")
      (description "INDUCTOR;4.3NH;2%;7.15GHZ SRF;90Q @1.7GHZ;.050 DCR;1.6A;0402")
      (fields (field (name "APPROVED") "CL"))
      (libsource (lib "Giga-tronics") (part "LSA6-02430"))
    )
    (comp (ref "L260")
      (value "4.3nH")
      (footprint "IND-0402HP")
      (description "INDUCTOR;4.3NH;2%;7.15GHZ SRF;90Q @1.7GHZ;.050 DCR;1.6A;0402")
      (fields (field (name "APPROVED") "CL"))
      (libsource (lib "Giga-tronics") (part "LSA6-02430"))
    )
    (comp (ref "L261")
      (value "4.3nH")
      (footprint "IND-0402HP")
      (description "INDUCTOR;4.3NH;2%;7.15GHZ SRF;90Q @1.7GHZ;.050 DCR;1.6A;0402")
      (fields (field (name "APPROVED") "CL"))
      (libsource (lib "Giga-tronics") (part "LSA6-02430"))
    )
    (comp (ref "L262")
      (value "4.3nH")
      (footprint "IND-0402HP")
      (description "INDUCTOR;4.3NH;2%;7.15GHZ SRF;90Q @1.7GHZ;.050 DCR;1.6A;0402")
      (fields (field (name "APPROVED") "CL"))
      (libsource (lib "Giga-tronics") (part "LSA6-02430"))
    )
    (comp (ref "L263")
      (value "4.3nH")
      (footprint "IND-0402HP")
      (description "INDUCTOR;4.3NH;2%;7.15GHZ SRF;90Q @1.7GHZ;.050 DCR;1.6A;0402")
      (fields (field (name "APPROVED") "CL"))
      (libsource (lib "Giga-tronics") (part "LSA6-02430"))
    )
    (comp (ref "L264")
      (value "4.3nH")
      (footprint "IND-0402HP")
      (description "INDUCTOR;4.3NH;2%;7.15GHZ SRF;90Q @1.7GHZ;.050 DCR;1.6A;0402")
      (fields (field (name "APPROVED") "CL"))
      (libsource (lib "Giga-tronics") (part "LSA6-02430"))
    )
    (comp (ref "NT1")
      (value "3 way net tie junction T shape")
      (footprint "3wayT_LP")
      (fields (field (name "NOLOAD") "N/L"))
      (libsource (lib "NetTie") (part "3wayT"))
    )
    (comp (ref "NT3")
      (value "3 way net tie junction T shape")
      (footprint "3wayT_LP")
      (fields (field (name "NOLOAD") "N/L"))
      (libsource (lib "NetTie") (part "3wayT"))
    )
    (comp (ref "Q1")
      (value "5A;25V VCEO;12.5W;45 MIN HFE;DPAK")
      (footprint "TO-252_DPAK_REVA")
      (fields (field (name "G_PN") "QBNP-00200") (field (name "APPROVED") "CL"))
      (libsource (lib "Giga-tronics") (part "QBNP-00200"))
    )
    (comp (ref "R15")
      (value "10.0K")
      (footprint "RES-0402-N")
      (description "10.0K OHMS;.06W;1%;200PPM;FILM;CHIP;0402")
      (fields (field (name "APPROVED") "CL"))
      (libsource (lib "Giga-tronics") (part "RK35-21000"))
    )
    (comp (ref "R18")
      (value "4.99K")
      (footprint "RES-0402-N")
      (description "4.99K OHMS;.06W;1%;200PPM;FILM;CHIP;0402")
      (fields (field (name "APPROVED") "CL"))
      (libsource (lib "Giga-tronics") (part "RK35-14990"))
    )
    (comp (ref "R19")
      (value "13.3k")
      (footprint "RES-0402-N")
      (description "13.3K OHMS;.06W;1%;200PPM;FILM;CHIP;0402")
      (fields (field (name "APPROVED") "CL"))
      (libsource (lib "Giga-tronics") (part "RK35-21330"))
    )
    (comp (ref "R21")
      (value "604")
      (footprint "RES-0402-N")
      (description "604 OHMS; 1%; .1W; 100PPM; FILM; CHIP; 0402")
      (fields (field (name "APPROVED") "CL"))
      (libsource (lib "Giga-tronics") (part "RK35-06040"))
    )
    (comp (ref "R24")
      (value "49.9")
      (footprint "RES-0603-N")
      (description "49.9 OHMS; 1%; .1W; 100PPM; FILM; CHIP; 0603")
      (fields (field (name "APPROVED") "CL"))
      (libsource (lib "Giga-tronics") (part "RK40-00499"))
    )
    (comp (ref "R25")
      (value "10.0K")
      (footprint "RES-0402-N")
      (description "10.0K Ohms;.06W;0.5%;±50PPM;CHIP RES;0402")
      (fields (field (name "APPROVED") "CL"))
      (libsource (lib "Giga-tronics") (part "RK36-21000"))
    )
    (comp (ref "R26")
      (value "10.0K")
      (footprint "RES-0402-N")
      (description "10.0K OHMS;.06W;1%;200PPM;FILM;CHIP;0402")
      (fields (field (name "APPROVED") "CL"))
      (libsource (lib "Giga-tronics") (part "RK35-21000"))
    )
    (comp (ref "R29")
      (value "10.0K")
      (footprint "RES-0402-N")
      (description "10.0K OHMS;.06W;1%;200PPM;FILM;CHIP;0402")
      (fields (field (name "APPROVED") "CL"))
      (libsource (lib "Giga-tronics") (part "RK35-21000"))
    )
    (comp (ref "R35")
      (value "4.99K")
      (footprint "RES-0402-N")
      (description "4.99K OHMS;.06W;1%;200PPM;FILM;CHIP;0402")
      (fields (field (name "APPROVED") "CL"))
      (libsource (lib "Giga-tronics") (part "RK35-14990"))
    )
    (comp (ref "R36")
      (value "4.99K")
      (footprint "RES-0402-N")
      (description "4.99K OHMS;.06W;1%;200PPM;FILM;CHIP;0402")
      (fields (field (name "APPROVED") "CL"))
      (libsource (lib "Giga-tronics") (part "RK35-14990"))
    )
    (comp (ref "R38")
      (value "15.4K")
      (footprint "RES-0402-N")
      (description "15.4K OHMS;.06W;1%;200PPM;FILM;CHIP;0402")
      (fields (field (name "APPROVED") "CL"))
      (libsource (lib "Giga-tronics") (part "RK35-21540"))
    )
    (comp (ref "R39")
      (value "13.3k")
      (footprint "RES-0402-N")
      (description "13.3K OHMS;.06W;1%;200PPM;FILM;CHIP;0402")
      (fields (field (name "APPROVED") "CL"))
      (libsource (lib "Giga-tronics") (part "RK35-21330"))
    )
    (comp (ref "R41")
      (value "332")
      (footprint "RES-0402-N")
      (description "332 OHMS; 1%; .1W; 100PPM; FILM; CHIP")
      (fields (field (name "APPROVED") "CL"))
      (libsource (lib "Giga-tronics") (part "RK35-03320"))
    )
    (comp (ref "R43")
      (value "475")
      (footprint "RES-0402-N")
      (description "475 OHMS; 1%; .1W; 100PPM; FILM; CHIP; 0402")
      (fields (field (name "APPROVED") "CL"))
      (libsource (lib "Giga-tronics") (part "RK35-04750"))
    )
    (comp (ref "R47")
      (value "10.0K")
      (footprint "RES-0402-N")
      (description "10.0K Ohms;.06W;0.5%;±50PPM;CHIP RES;0402")
      (fields (field (name "APPROVED") "CL"))
      (libsource (lib "Giga-tronics") (part "RK36-21000"))
    )
    (comp (ref "R48")
      (value "10.0K")
      (footprint "RES-0402-N")
      (description "10.0K Ohms;.06W;0.5%;±50PPM;CHIP RES;0402")
      (fields (field (name "APPROVED") "CL"))
      (libsource (lib "Giga-tronics") (part "RK36-21000"))
    )
    (comp (ref "R186")
      (value "750")
      (footprint "RES-0201-N")
      (description "750 OHMS;.05W;1%;100PPM;FILM CHIP;0201")
      (fields (field (name "APPROVED") "CL"))
      (libsource (lib "Giga-tronics") (part "RK30-07500"))
    )
    (comp (ref "R188")
      (value "750")
      (footprint "RES-0201-N")
      (description "750 OHMS;.05W;1%;100PPM;FILM CHIP;0201")
      (fields (field (name "APPROVED") "CL"))
      (libsource (lib "Giga-tronics") (part "RK30-07500"))
    )
    (comp (ref "R189")
      (value "10.0K")
      (footprint "RES-0402-N")
      (description "10.0K OHMS;.06W;1%;200PPM;FILM;CHIP;0402")
      (fields (field (name "APPROVED") "CL"))
      (libsource (lib "Giga-tronics") (part "RK35-21000"))
    )
    (comp (ref "R190")
      (value "4.99K")
      (footprint "RES-0402-N")
      (description "4.99K OHMS;.06W;1%;200PPM;FILM;CHIP;0402")
      (fields (field (name "APPROVED") "CL"))
      (libsource (lib "Giga-tronics") (part "RK35-14990"))
    )
    (comp (ref "R191")
      (value "13.3k")
      (footprint "RES-0402-N")
      (description "13.3K OHMS;.06W;1%;200PPM;FILM;CHIP;0402")
      (fields (field (name "APPROVED") "CL"))
      (libsource (lib "Giga-tronics") (part "RK35-21330"))
    )
    (comp (ref "R260")
      (value "475")
      (footprint "RES-0402-N")
      (description "475 OHMS; 1%; .1W; 100PPM; FILM; CHIP; 0402")
      (fields (field (name "APPROVED") "CL"))
      (libsource (lib "Giga-tronics") (part "RK35-04750"))
    )
    (comp (ref "R261")
      (value "10.0K")
      (footprint "RES-0402-N")
      (description "10.0K Ohms;.06W;0.5%;±50PPM;CHIP RES;0402")
      (fields (field (name "APPROVED") "CL"))
      (libsource (lib "Giga-tronics") (part "RK36-21000"))
    )
    (comp (ref "R279")
      (value "0")
      (footprint "RES-0402-N")
      (description "JUMPER;0 OHMS;SMT;0402")
      (fields (field (name "APPROVED") "CL"))
      (libsource (lib "Giga-tronics") (part "RK35-00000"))
    )
    (comp (ref "R281")
      (value "0")
      (footprint "RES-0402-N")
      (description "JUMPER;0 OHMS;SMT;0402")
      (fields (field (name "APPROVED") "CL"))
      (libsource (lib "Giga-tronics") (part "RK35-00000"))
    )
    (comp (ref "R328")
      (value "1.00K")
      (footprint "RES-0402-N")
      (description "1.0K OHMS;.06W;1%;200PPM;FILM;CHIP;0402")
      (fields (field (name "APPROVED") "CL"))
      (libsource (lib "Giga-tronics") (part "RK35-11000"))
    )
    (comp (ref "R383")
      (value "220 OHM; 25%; 1T; SMT; 2.75MMx2.2MM; TOP ADJ")
      (footprint "TRIM-PVA2")
      (fields (field (name "NOLOAD") "N/L") (field (name "APPROVED") "CL"))
      (libsource (lib "Giga-tronics") (part "RASA-02200"))
    )
    (comp (ref "R384")
      (value "220 OHM; 25%; 1T; SMT; 2.75MMx2.2MM; TOP ADJ")
      (footprint "TRIM-PVA2")
      (fields (field (name "NOLOAD") "N/L") (field (name "APPROVED") "CL"))
      (libsource (lib "Giga-tronics") (part "RASA-02200"))
    )
    (comp (ref "R675")
      (value "10.0K")
      (footprint "RES-0402-N")
      (description "10.0K OHMS;.06W;1%;200PPM;FILM;CHIP;0402")
      (fields (field (name "APPROVED") "CL"))
      (libsource (lib "Giga-tronics") (part "RK35-21000"))
    )
    (comp (ref "R677")
      (value "4.99K")
      (footprint "RES-0402-N")
      (description "4.99K OHMS;.06W;1%;200PPM;FILM;CHIP;0402")
      (fields (field (name "APPROVED") "CL"))
      (libsource (lib "Giga-tronics") (part "RK35-14990"))
    )
    (comp (ref "R678")
      (value "2.74K")
      (footprint "RES-0402-N")
      (description "2.74K OHMS;.06W;1%;100PPM;FILM;CHIP;0402")
      (fields (field (name "APPROVED") "CL"))
      (libsource (lib "Giga-tronics") (part "RK35-12740"))
    )
    (comp (ref "R679")
      (value "1.21K")
      (footprint "RES-0402-N")
      (description "1.21K OHMS;.06W;1%;200PPM;FILM;CHIP;0402")
      (fields (field (name "APPROVED") "CL"))
      (libsource (lib "Giga-tronics") (part "RK35-11210"))
    )
    (comp (ref "R681")
      (value "10.0K")
      (footprint "RES-0402-N")
      (description "10.0K Ohms;.06W;0.5%;±50PPM;CHIP RES;0402")
      (fields (field (name "APPROVED") "CL"))
      (libsource (lib "Giga-tronics") (part "RK36-21000"))
    )
    (comp (ref "T1")
      (value "A1-A1: T1")
      (footprint "JIB0-11254")
      (description "SOCKET;SINGLE;.018-.040 ID X .254;OPEN;GLD")
      (fields (field (name "APPROVED") "NM"))
      (libsource (lib "Giga-tronics") (part "JIB0-11254"))
    )
    (comp (ref "T14")
      (value "A1-A1: T14 (A9g)")
      (footprint "JIB0-11254")
      (description "SOCKET;SINGLE;.018-.040 ID X .254;OPEN;GLD")
      (fields (field (name "APPROVED") "NM"))
      (libsource (lib "Giga-tronics") (part "JIB0-11254"))
    )
    (comp (ref "T15")
      (value "A1-A1: T15 (A9d)")
      (footprint "JIB0-11254")
      (description "SOCKET;SINGLE;.018-.040 ID X .254;OPEN;GLD")
      (fields (field (name "APPROVED") "NM"))
      (libsource (lib "Giga-tronics") (part "JIB0-11254"))
    )
    (comp (ref "T16")
      (value "A1-A1: T16 (A15g)")
      (footprint "JIB0-11254")
      (description "SOCKET;SINGLE;.018-.040 ID X .254;OPEN;GLD")
      (fields (field (name "APPROVED") "NM"))
      (libsource (lib "Giga-tronics") (part "JIB0-11254"))
    )
    (comp (ref "T17")
      (value "A1-A1: T17 (A15d)")
      (footprint "JIB0-11254")
      (description "SOCKET;SINGLE;.018-.040 ID X .254;OPEN;GLD")
      (fields (field (name "APPROVED") "NM"))
      (libsource (lib "Giga-tronics") (part "JIB0-11254"))
    )
    (comp (ref "T34")
      (value "A1-A1: T34 (A16g)")
      (footprint "JIB0-11254")
      (description "SOCKET;SINGLE;.018-.040 ID X .254;OPEN;GLD")
      (fields (field (name "APPROVED") "NM"))
      (libsource (lib "Giga-tronics") (part "JIB0-11254"))
    )
    (comp (ref "T35")
      (value "A1-A1: T35 (A16d)")
      (footprint "JIB0-11254")
      (description "SOCKET;SINGLE;.018-.040 ID X .254;OPEN;GLD")
      (fields (field (name "APPROVED") "NM"))
      (libsource (lib "Giga-tronics") (part "JIB0-11254"))
    )
    (comp (ref "T36")
      (value "A1-A1: T36 (A11d)")
      (footprint "JIB0-11254")
      (description "SOCKET;SINGLE;.018-.040 ID X .254;OPEN;GLD")
      (fields (field (name "APPROVED") "NM"))
      (libsource (lib "Giga-tronics") (part "JIB0-11254"))
    )
    (comp (ref "T37")
      (value "A1-A1: T37 (A11g)")
      (footprint "JIB0-11254")
      (description "SOCKET;SINGLE;.018-.040 ID X .254;OPEN;GLD")
      (fields (field (name "APPROVED") "NM"))
      (libsource (lib "Giga-tronics") (part "JIB0-11254"))
    )
    (comp (ref "T38")
      (value "A1-A1: T38")
      (footprint "JIB0-11254")
      (description "SOCKET;SINGLE;.018-.040 ID X .254;OPEN;GLD")
      (fields (field (name "APPROVED") "NM"))
      (libsource (lib "Giga-tronics") (part "JIB0-11254"))
    )
    (comp (ref "T39")
      (value "A1-A1: T39 (A12d)")
      (footprint "JIB0-11254")
      (description "SOCKET;SINGLE;.018-.040 ID X .254;OPEN;GLD")
      (fields (field (name "APPROVED") "NM"))
      (libsource (lib "Giga-tronics") (part "JIB0-11254"))
    )
    (comp (ref "T40")
      (value "A1-A1: T40 (A12g)")
      (footprint "JIB0-11254")
      (description "SOCKET;SINGLE;.018-.040 ID X .254;OPEN;GLD")
      (fields (field (name "APPROVED") "NM"))
      (libsource (lib "Giga-tronics") (part "JIB0-11254"))
    )
    (comp (ref "T43")
      (value "A1-A1: T43")
      (footprint "JIB0-11254")
      (description "SOCKET;SINGLE;.018-.040 ID X .254;OPEN;GLD")
      (fields (field (name "APPROVED") "NM"))
      (libsource (lib "Giga-tronics") (part "JIB0-11254"))
    )
    (comp (ref "T44")
      (value "A1-A1: T44")
      (footprint "JIB0-11254")
      (description "SOCKET;SINGLE;.018-.040 ID X .254;OPEN;GLD")
      (fields (field (name "APPROVED") "NM"))
      (libsource (lib "Giga-tronics") (part "JIB0-11254"))
    )
    (comp (ref "T49")
      (value "A1-A1: T49 (A13g)")
      (footprint "JIB0-11254")
      (description "SOCKET;SINGLE;.018-.040 ID X .254;OPEN;GLD")
      (fields (field (name "APPROVED") "NM"))
      (libsource (lib "Giga-tronics") (part "JIB0-11254"))
    )
    (comp (ref "T50")
      (value "A1-A1: T50 (A13d)")
      (footprint "JIB0-11254")
      (description "SOCKET;SINGLE;.018-.040 ID X .254;OPEN;GLD")
      (fields (field (name "APPROVED") "NM"))
      (libsource (lib "Giga-tronics") (part "JIB0-11254"))
    )
    (comp (ref "T53")
      (value "A1-A1: T53")
      (footprint "JIB0-11254")
      (description "SOCKET;SINGLE;.018-.040 ID X .254;OPEN;GLD")
      (fields (field (name "APPROVED") "NM"))
      (libsource (lib "Giga-tronics") (part "JIB0-11254"))
    )
    (comp (ref "T54")
      (value "A1-A1: T54")
      (footprint "JIB0-11254")
      (description "SOCKET;SINGLE;.018-.040 ID X .254;OPEN;GLD")
      (fields (field (name "APPROVED") "NM"))
      (libsource (lib "Giga-tronics") (part "JIB0-11254"))
    )
    (comp (ref "T55")
      (value "A1-A1: T55")
      (footprint "JIB0-11254")
      (description "SOCKET;SINGLE;.018-.040 ID X .254;OPEN;GLD")
      (fields (field (name "APPROVED") "NM"))
      (libsource (lib "Giga-tronics") (part "JIB0-11254"))
    )
    (comp (ref "T70")
      (value "A1-A1: T70 (A10d)")
      (footprint "JIB0-11254")
      (description "SOCKET;SINGLE;.018-.040 ID X .254;OPEN;GLD")
      (fields (field (name "APPROVED") "NM"))
      (libsource (lib "Giga-tronics") (part "JIB0-11254"))
    )
    (comp (ref "T71")
      (value "A1-A1: T71 (A10g)")
      (footprint "JIB0-11254")
      (description "SOCKET;SINGLE;.018-.040 ID X .254;OPEN;GLD")
      (fields (field (name "APPROVED") "NM"))
      (libsource (lib "Giga-tronics") (part "JIB0-11254"))
    )
    (comp (ref "T72")
      (value "A1-A1: T72")
      (footprint "JIB0-11254")
      (description "SOCKET;SINGLE;.018-.040 ID X .254;OPEN;GLD")
      (fields (field (name "APPROVED") "NM"))
      (libsource (lib "Giga-tronics") (part "JIB0-11254"))
    )
    (comp (ref "T77")
      (value "A1-A1: T77")
      (footprint "JIB0-11254")
      (description "SOCKET;SINGLE;.018-.040 ID X .254;OPEN;GLD")
      (fields (field (name "APPROVED") "NM"))
      (libsource (lib "Giga-tronics") (part "JIB0-11254"))
    )
    (comp (ref "T78")
      (value "A1-A1: T78")
      (footprint "JIB0-11254")
      (description "SOCKET;SINGLE;.018-.040 ID X .254;OPEN;GLD")
      (fields (field (name "APPROVED") "NM"))
      (libsource (lib "Giga-tronics") (part "JIB0-11254"))
    )
    (comp (ref "T79")
      (value "A1-A1: T79")
      (footprint "JIB0-11254")
      (description "SOCKET;SINGLE;.018-.040 ID X .254;OPEN;GLD")
      (fields (field (name "APPROVED") "NM"))
      (libsource (lib "Giga-tronics") (part "JIB0-11254"))
    )
    (comp (ref "T84")
      (value "A1-A1: T84")
      (footprint "JIB0-11254-TRIM")
      (description "SOCKET;SINGLE;.018-.040 ID X .254;OPEN;GLD")
      (fields (field (name "G_PN") "JIB0-11254"))
      (libsource (lib "Giga-tronics") (part "JIB0-11254_Trim"))
    )
    (comp (ref "TP1")
      (value ".")
      (footprint "TP-060")
      (fields (field (name "NOLOAD") "N/L") (field (name "APPROVED") "NM"))
      (libsource (lib "Giga-tronics") (part "TP-060"))
    )
    (comp (ref "TP3")
      (value ".")
      (footprint "TP-060")
      (fields (field (name "NOLOAD") "N/L") (field (name "APPROVED") "NM"))
      (libsource (lib "Giga-tronics") (part "TP-060"))
    )
    (comp (ref "TP4")
      (value ".")
      (footprint "TP-060")
      (fields (field (name "NOLOAD") "N/L") (field (name "APPROVED") "NM"))
      (libsource (lib "Giga-tronics") (part "TP-060"))
    )
    (comp (ref "TP5")
      (value ".")
      (footprint "TP-060")
      (fields (field (name "NOLOAD") "N/L") (field (name "APPROVED") "NM"))
      (libsource (lib "Giga-tronics") (part "TP-060"))
    )
    (comp (ref "TP6")
      (value ".")
      (footprint "TP-060")
      (fields (field (name "NOLOAD") "N/L") (field (name "APPROVED") "NM"))
      (libsource (lib "Giga-tronics") (part "TP-060"))
    )
    (comp (ref "TP7")
      (value ".")
      (footprint "TP-060")
      (fields (field (name "NOLOAD") "N/L") (field (name "APPROVED") "NM"))
      (libsource (lib "Giga-tronics") (part "TP-060"))
    )
    (comp (ref "TP8")
      (value ".")
      (footprint "TP-060")
      (fields (field (name "NOLOAD") "N/L") (field (name "APPROVED") "NM"))
      (libsource (lib "Giga-tronics") (part "TP-060"))
    )
    (comp (ref "TP12")
      (value ".")
      (footprint "TP-060")
      (fields (field (name "NOLOAD") "N/L") (field (name "APPROVED") "NM"))
      (libsource (lib "Giga-tronics") (part "TP-060"))
    )
    (comp (ref "TP13")
      (value ".")
      (footprint "TP-060")
      (fields (field (name "NOLOAD") "N/L") (field (name "APPROVED") "NM"))
      (libsource (lib "Giga-tronics") (part "TP-060"))
    )
    (comp (ref "TP14")
      (value ".")
      (footprint "TP-060")
      (fields (field (name "NOLOAD") "N/L") (field (name "APPROVED") "NM"))
      (libsource (lib "Giga-tronics") (part "TP-060"))
    )
    (comp (ref "TP16")
      (value ".")
      (footprint "TP-060")
      (fields (field (name "NOLOAD") "N/L") (field (name "APPROVED") "NM"))
      (libsource (lib "Giga-tronics") (part "TP-060"))
    )
    (comp (ref "TP49")
      (value ".")
      (footprint "TP-060")
      (fields (field (name "NOLOAD") "N/L") (field (name "APPROVED") "NM"))
      (libsource (lib "Giga-tronics") (part "TP-060"))
    )
    (comp (ref "TP50")
      (value ".")
      (footprint "TP-060")
      (fields (field (name "NOLOAD") "N/L") (field (name "APPROVED") "NM"))
      (libsource (lib "Giga-tronics") (part "TP-060"))
    )
    (comp (ref "U30")
      (value "ULD0-00920_1")
      (footprint "LP5E_HITTITE_NO_VIAS")
      (description "HMC920LP5E ACTIVE BIAS CONTROLLER;1 OUT;16.5V MAX IN;QFN-32")
      (fields
        (field (name "G_PN") "ULD0-00920")
        (field (name "CLASSNAME") "ABb")
        (field (name "APPROVED") "CL")
      )
      (libsource (lib "Giga-tronics") (part "ULD0-00920_1"))
    )
    (comp (ref "U38")
      (value "ULD0-00920")
      (footprint "LP5E_HITTITE")
      (description "HMC920LP5E ACTIVE BIAS CONTROLLER;1 OUT;16.5V MAX IN;QFN-32")
      (fields
        (field (name "G_PN") "ULD0-00920")
        (field (name "M_PN") "HMC920LP5E")
        (field (name "CLASSNAME") "ABa")
        (field (name "APPROVED") "CL")
      )
      (libsource (lib "Giga-tronics") (part "ULD0-00920"))
    )
    (comp (ref "U64")
      (value "ULD0-00920")
      (footprint "LP5E_HITTITE")
      (description "HMC920LP5E ACTIVE BIAS CONTROLLER;1 OUT;16.5V MAX IN;QFN-32")
      (fields
        (field (name "G_PN") "ULD0-00920")
        (field (name "M_PN") "HMC920LP5E")
        (field (name "CLASSNAME") "ABb")
        (field (name "APPROVED") "CL")
      )
      (libsource (lib "Giga-tronics") (part "ULD0-00920"))
    )
    (comp (ref "U77")
      (value "ULD0-00920")
      (footprint "LP5E_HITTITE")
      (description "HMC920LP5E ACTIVE BIAS CONTROLLER;1 OUT;16.5V MAX IN;QFN-32")
      (fields
        (field (name "G_PN") "ULD0-00920")
        (field (name "M_PN") "HMC920LP5E")
        (field (name "CLASSNAME") "ABd")
        (field (name "APPROVED") "CL")
      )
      (libsource (lib "Giga-tronics") (part "ULD0-00920"))
    )
    (comp (ref "U78")
      (value "ULD0-00920")
      (footprint "LP5E_HITTITE")
      (description "HMC920LP5E ACTIVE BIAS CONTROLLER;1 OUT;16.5V MAX IN;QFN-32")
      (fields
        (field (name "G_PN") "ULD0-00920")
        (field (name "M_PN") "HMC920LP5E")
        (field (name "CLASSNAME") "ABc")
        (field (name "APPROVED") "CL")
      )
      (libsource (lib "Giga-tronics") (part "ULD0-00920"))
    )
  )
  (nets
    (net (code "1") (name "+3V_A1-A1") (class "Default")
      (node (ref "FL109") (pin "1") (pinfunction "IN_1") (pintype "passive"))
      (node (ref "FL116") (pin "1") (pinfunction "IN_1") (pintype "passive"))
      (node (ref "FT25") (pin "1") (pinfunction "1_1") (pintype "passive"))
      (node (ref "TP5") (pin "1") (pinfunction "1_1") (pintype "passive"))
    )
    (net (code "2") (name "+5V_A1-A1") (class "Default")
      (node (ref "FL102") (pin "1") (pinfunction "IN_1") (pintype "passive"))
      (node (ref "FL104") (pin "1") (pinfunction "IN_1") (pintype "passive"))
      (node (ref "FL111") (pin "1") (pinfunction "IN_1") (pintype "passive"))
      (node (ref "FL118") (pin "1") (pinfunction "IN_1") (pintype "passive"))
      (node (ref "FL123") (pin "1") (pinfunction "IN_1") (pintype "passive"))
      (node (ref "FL127") (pin "1") (pinfunction "IN_1") (pintype "passive"))
      (node (ref "FL129") (pin "1") (pinfunction "IN_1") (pintype "passive"))
      (node (ref "FL97") (pin "1") (pinfunction "IN_1") (pintype "passive"))
      (node (ref "FT22") (pin "1") (pinfunction "1_1") (pintype "passive"))
      (node (ref "TP1") (pin "1") (pinfunction "1_1") (pintype "passive"))
    )
    (net (code "3") (name "+6V_FETs") (class "Default")
      (node (ref "C1001") (pin "1") (pinfunction "POS_1") (pintype "passive"))
      (node (ref "C1002") (pin "1") (pinfunction "POS_1") (pintype "passive"))
      (node (ref "C1007") (pin "2") (pintype "passive"))
      (node (ref "C1008") (pin "2") (pintype "passive"))
      (node (ref "C1015") (pin "1") (pinfunction "POS_1") (pintype "passive"))
      (node (ref "C1021") (pin "2") (pintype "passive"))
      (node (ref "C1025") (pin "2") (pintype "passive"))
      (node (ref "C1026") (pin "2") (pintype "passive"))
      (node (ref "C1030") (pin "2") (pintype "passive"))
      (node (ref "C73") (pin "1") (pinfunction "POS_1") (pintype "passive"))
      (node (ref "C80") (pin "2") (pintype "passive"))
      (node (ref "C93") (pin "2") (pintype "passive"))
      (node (ref "C983") (pin "1") (pinfunction "POS_1") (pintype "passive"))
      (node (ref "C985") (pin "2") (pintype "passive"))
      (node (ref "C990") (pin "2") (pintype "passive"))
      (node (ref "FT1") (pin "1") (pinfunction "1_1") (pintype "passive"))
      (node (ref "U30") (pin "1") (pinfunction "VDD1_1") (pintype "passive"))
      (node (ref "U30") (pin "14") (pinfunction "VDD2_14") (pintype "passive"))
      (node (ref "U30") (pin "2") (pinfunction "VDD1_2") (pintype "passive"))
      (node (ref "U38") (pin "1") (pinfunction "VDD1_1") (pintype "passive"))
      (node (ref "U38") (pin "14") (pinfunction "VDD2_14") (pintype "passive"))
      (node (ref "U38") (pin "2") (pinfunction "VDD1_2") (pintype "passive"))
      (node (ref "U64") (pin "1") (pinfunction "VDD1_1") (pintype "passive"))
      (node (ref "U64") (pin "14") (pinfunction "VDD2_14") (pintype "passive"))
      (node (ref "U64") (pin "2") (pinfunction "VDD1_2") (pintype "passive"))
      (node (ref "U77") (pin "1") (pinfunction "VDD1_1") (pintype "passive"))
      (node (ref "U77") (pin "14") (pinfunction "VDD2_14") (pintype "passive"))
      (node (ref "U77") (pin "2") (pinfunction "VDD1_2") (pintype "passive"))
      (node (ref "U78") (pin "1") (pinfunction "VDD1_1") (pintype "passive"))
      (node (ref "U78") (pin "14") (pinfunction "VDD2_14") (pintype "passive"))
      (node (ref "U78") (pin "2") (pinfunction "VDD1_2") (pintype "passive"))
    )
    (net (code "4") (name "/T1") (class "Default")
      (node (ref "C65") (pin "1") (pintype "passive"))
      (node (ref "FL96") (pin "3") (pintype "passive"))
      (node (ref "T1") (pin "1") (pintype "passive"))
    )
    (net (code "5") (name "/T14") (class "Default")
      (node (ref "C1004") (pin "2") (pintype "passive"))
      (node (ref "NT3") (pin "2") (pinfunction "2_2") (pintype "passive"))
      (node (ref "T14") (pin "1") (pintype "passive"))
    )
    (net (code "6") (name "/T15") (class "Default")
      (node (ref "C1016") (pin "2") (pintype "passive"))
      (node (ref "T15") (pin "1") (pintype "passive"))
      (node (ref "U77") (pin "22") (pinfunction "VDRAIN_22") (pintype "passive"))
    )
    (net (code "7") (name "/T16") (class "Default")
      (node (ref "C984") (pin "2") (pintype "passive"))
      (node (ref "NT1") (pin "2") (pinfunction "2_2") (pintype "passive"))
      (node (ref "T16") (pin "1") (pintype "passive"))
    )
    (net (code "8") (name "/T17") (class "Default")
      (node (ref "C988") (pin "2") (pintype "passive"))
      (node (ref "T17") (pin "1") (pintype "passive"))
      (node (ref "U38") (pin "22") (pinfunction "VDRAIN_22") (pintype "passive"))
    )
    (net (code "9") (name "/T34") (class "Default")
      (node (ref "C867") (pin "1") (pintype "passive"))
      (node (ref "C986") (pin "1") (pintype "passive"))
      (node (ref "NT1") (pin "1") (pinfunction "1_1") (pintype "passive"))
      (node (ref "T34") (pin "1") (pintype "passive"))
      (node (ref "TP7") (pin "1") (pinfunction "1_1") (pintype "passive"))
    )
    (net (code "10") (name "/T35") (class "Default")
      (node (ref "C1049") (pin "2") (pintype "passive"))
      (node (ref "T35") (pin "1") (pintype "passive"))
      (node (ref "TP3") (pin "1") (pinfunction "1_1") (pintype "passive"))
      (node (ref "U38") (pin "23") (pinfunction "VDRAIN_23") (pintype "passive"))
    )
    (net (code "11") (name "/T36") (class "Default")
      (node (ref "C87") (pin "2") (pintype "passive"))
      (node (ref "L263") (pin "2") (pinfunction "2_2") (pintype "passive"))
      (node (ref "T36") (pin "1") (pintype "passive"))
    )
    (net (code "12") (name "/T37") (class "Default")
      (node (ref "C74") (pin "2") (pintype "passive"))
      (node (ref "T37") (pin "1") (pintype "passive"))
      (node (ref "TP50") (pin "1") (pinfunction "1_1") (pintype "passive"))
      (node (ref "U30") (pin "21") (pinfunction "VGATE_21") (pintype "passive"))
    )
    (net (code "13") (name "/T38") (class "Default")
      (node (ref "C70") (pin "1") (pintype "passive"))
      (node (ref "FL101") (pin "3") (pintype "passive"))
      (node (ref "T38") (pin "1") (pintype "passive"))
    )
    (net (code "14") (name "/T39") (class "Default")
      (node (ref "C1060") (pin "2") (pintype "passive"))
      (node (ref "L262") (pin "2") (pinfunction "2_2") (pintype "passive"))
      (node (ref "T39") (pin "1") (pintype "passive"))
    )
    (net (code "15") (name "/T40") (class "Default")
      (node (ref "C81") (pin "1") (pintype "passive"))
      (node (ref "T40") (pin "1") (pintype "passive"))
      (node (ref "TP8") (pin "1") (pinfunction "1_1") (pintype "passive"))
      (node (ref "U64") (pin "21") (pinfunction "VGATE_21") (pintype "passive"))
    )
    (net (code "16") (name "/T43") (class "Default")
      (node (ref "C84") (pin "1") (pintype "passive"))
      (node (ref "FL115") (pin "3") (pintype "passive"))
      (node (ref "T43") (pin "1") (pintype "passive"))
    )
    (net (code "17") (name "/T44") (class "Default")
      (node (ref "C77") (pin "1") (pintype "passive"))
      (node (ref "FL108") (pin "3") (pintype "passive"))
      (node (ref "T44") (pin "1") (pintype "passive"))
    )
    (net (code "18") (name "/T49") (class "Default")
      (node (ref "C1005") (pin "2") (pintype "passive"))
      (node (ref "C1011") (pin "1") (pintype "passive"))
      (node (ref "T49") (pin "1") (pintype "passive"))
      (node (ref "TP14") (pin "1") (pinfunction "1_1") (pintype "passive"))
      (node (ref "U78") (pin "21") (pinfunction "VGATE_21") (pintype "passive"))
    )
    (net (code "19") (name "/T50") (class "Default")
      (node (ref "C1017") (pin "2") (pintype "passive"))
      (node (ref "T50") (pin "1") (pintype "passive"))
      (node (ref "TP13") (pin "1") (pinfunction "1_1") (pintype "passive"))
      (node (ref "U78") (pin "22") (pinfunction "VDRAIN_22") (pintype "passive"))
      (node (ref "U78") (pin "23") (pinfunction "VDRAIN_23") (pintype "passive"))
    )
    (net (code "20") (name "/T53") (class "Default")
      (node (ref "C1000") (pin "1") (pintype "passive"))
      (node (ref "C1006") (pin "1") (pintype "passive"))
      (node (ref "L261") (pin "2") (pinfunction "2_2") (pintype "passive"))
      (node (ref "R188") (pin "2") (pintype "passive"))
      (node (ref "T53") (pin "1") (pintype "passive"))
    )
    (net (code "21") (name "/T54") (class "Default")
      (node (ref "L260") (pin "2") (pinfunction "2_2") (pintype "passive"))
      (node (ref "T54") (pin "1") (pintype "passive"))
    )
    (net (code "22") (name "/T55") (class "Default")
      (node (ref "L264") (pin "2") (pinfunction "2_2") (pintype "passive"))
      (node (ref "T55") (pin "1") (pintype "passive"))
    )
    (net (code "23") (name "/T70") (class "Default")
      (node (ref "C1018") (pin "2") (pintype "passive"))
      (node (ref "T70") (pin "1") (pintype "passive"))
      (node (ref "TP12") (pin "1") (pinfunction "1_1") (pintype "passive"))
      (node (ref "U77") (pin "23") (pinfunction "VDRAIN_23") (pintype "passive"))
    )
    (net (code "24") (name "/T71") (class "Default")
      (node (ref "C1010") (pin "1") (pintype "passive"))
      (node (ref "NT3") (pin "1") (pinfunction "1_1") (pintype "passive"))
      (node (ref "T71") (pin "1") (pintype "passive"))
      (node (ref "TP16") (pin "1") (pinfunction "1_1") (pintype "passive"))
    )
    (net (code "25") (name "/T72") (class "Default")
      (node (ref "C79") (pin "1") (pintype "passive"))
      (node (ref "FL110") (pin "3") (pintype "passive"))
      (node (ref "T72") (pin "1") (pintype "passive"))
    )
    (net (code "26") (name "/T77") (class "Default") (node (ref "T77") (pin "1") (pintype "passive")))
    (net (code "27") (name "/T78") (class "Default") (node (ref "T78") (pin "1") (pintype "passive")))
    (net (code "28") (name "/T79") (class "Default")
      (node (ref "C72") (pin "1") (pintype "passive"))
      (node (ref "FL103") (pin "3") (pintype "passive"))
      (node (ref "T79") (pin "1") (pintype "passive"))
    )
    (net (code "29") (name "/T84") (class "Default")
      (node (ref "C960") (pin "1") (pintype "passive"))
      (node (ref "L259") (pin "2") (pinfunction "2_2") (pintype "passive"))
      (node (ref "R186") (pin "2") (pintype "passive"))
      (node (ref "T84") (pin "1") (pintype "passive"))
    )
    (net (code "30") (name "GND") (class "Default")
      (node (ref "C100") (pin "1") (pintype "passive"))
      (node (ref "C1000") (pin "2") (pintype "passive"))
      (node (ref "C1001") (pin "2") (pinfunction "NEG_2") (pintype "passive"))
      (node (ref "C1002") (pin "2") (pinfunction "NEG_2") (pintype "passive"))
      (node (ref "C1003") (pin "2") (pintype "passive"))
      (node (ref "C1004") (pin "1") (pintype "passive"))
      (node (ref "C1005") (pin "1") (pintype "passive"))
      (node (ref "C1006") (pin "2") (pintype "passive"))
      (node (ref "C1007") (pin "1") (pintype "passive"))
      (node (ref "C1008") (pin "1") (pintype "passive"))
      (node (ref "C1009") (pin "2") (pintype "passive"))
      (node (ref "C1010") (pin "2") (pintype "passive"))
      (node (ref "C1011") (pin "2") (pintype "passive"))
      (node (ref "C1012") (pin "2") (pinfunction "NEG_2") (pintype "passive"))
      (node (ref "C1013") (pin "2") (pinfunction "NEG_2") (pintype "passive"))
      (node (ref "C1014") (pin "2") (pinfunction "NEG_2") (pintype "passive"))
      (node (ref "C1015") (pin "2") (pinfunction "NEG_2") (pintype "passive"))
      (node (ref "C1016") (pin "1") (pintype "passive"))
      (node (ref "C1017") (pin "1") (pintype "passive"))
      (node (ref "C1018") (pin "1") (pintype "passive"))
      (node (ref "C1021") (pin "1") (pintype "passive"))
      (node (ref "C1022") (pin "1") (pintype "passive"))
      (node (ref "C1023") (pin "1") (pintype "passive"))
      (node (ref "C1024") (pin "2") (pinfunction "NEG_2") (pintype "passive"))
      (node (ref "C1025") (pin "1") (pintype "passive"))
      (node (ref "C1026") (pin "1") (pintype "passive"))
      (node (ref "C1028") (pin "1") (pintype "passive"))
      (node (ref "C1029") (pin "1") (pintype "passive"))
      (node (ref "C1030") (pin "1") (pintype "passive"))
      (node (ref "C1031") (pin "1") (pintype "passive"))
      (node (ref "C1032") (pin "1") (pintype "passive"))
      (node (ref "C1049") (pin "1") (pintype "passive"))
      (node (ref "C1060") (pin "1") (pintype "passive"))
      (node (ref "C64") (pin "2") (pintype "passive"))
      (node (ref "C65") (pin "2") (pintype "passive"))
      (node (ref "C66") (pin "2") (pintype "passive"))
      (node (ref "C67") (pin "2") (pinfunction "NEG_2") (pintype "passive"))
      (node (ref "C69") (pin "2") (pintype "passive"))
      (node (ref "C70") (pin "2") (pintype "passive"))
      (node (ref "C71") (pin "2") (pintype "passive"))
      (node (ref "C72") (pin "2") (pintype "passive"))
      (node (ref "C73") (pin "2") (pinfunction "NEG_2") (pintype "passive"))
      (node (ref "C74") (pin "1") (pintype "passive"))
      (node (ref "C76") (pin "2") (pintype "passive"))
      (node (ref "C77") (pin "2") (pintype "passive"))
      (node (ref "C78") (pin "2") (pintype "passive"))
      (node (ref "C79") (pin "2") (pintype "passive"))
      (node (ref "C80") (pin "1") (pintype "passive"))
      (node (ref "C81") (pin "2") (pintype "passive"))
      (node (ref "C82") (pin "2") (pinfunction "NEG_2") (pintype "passive"))
      (node (ref "C83") (pin "2") (pintype "passive"))
      (node (ref "C84") (pin "2") (pintype "passive"))
      (node (ref "C85") (pin "2") (pintype "passive"))
      (node (ref "C86") (pin "2") (pintype "passive"))
      (node (ref "C867") (pin "2") (pintype "passive"))
      (node (ref "C87") (pin "1") (pintype "passive"))
      (node (ref "C870") (pin "2") (pintype "passive"))
      (node (ref "C89") (pin "1") (pintype "passive"))
      (node (ref "C90") (pin "2") (pintype "passive"))
      (node (ref "C91") (pin "2") (pintype "passive"))
      (node (ref "C93") (pin "1") (pintype "passive"))
      (node (ref "C94") (pin "2") (pintype "passive"))
      (node (ref "C95") (pin "2") (pintype "passive"))
      (node (ref "C96") (pin "2") (pintype "passive"))
      (node (ref "C960") (pin "2") (pintype "passive"))
      (node (ref "C97") (pin "2") (pintype "passive"))
      (node (ref "C981") (pin "2") (pinfunction "NEG_2") (pintype "passive"))
      (node (ref "C982") (pin "2") (pintype "passive"))
      (node (ref "C983") (pin "2") (pinfunction "NEG_2") (pintype "passive"))
      (node (ref "C984") (pin "1") (pintype "passive"))
      (node (ref "C985") (pin "1") (pintype "passive"))
      (node (ref "C986") (pin "2") (pintype "passive"))
      (node (ref "C987") (pin "2") (pinfunction "NEG_2") (pintype "passive"))
      (node (ref "C988") (pin "1") (pintype "passive"))
      (node (ref "C990") (pin "1") (pintype "passive"))
      (node (ref "C992") (pin "1") (pintype "passive"))
      (node (ref "C993") (pin "1") (pintype "passive"))
      (node (ref "C994") (pin "1") (pintype "passive"))
      (node (ref "C995") (pin "2") (pintype "passive"))
      (node (ref "C996") (pin "2") (pintype "passive"))
      (node (ref "C997") (pin "2") (pintype "passive"))
      (node (ref "C998") (pin "2") (pinfunction "NEG_2") (pintype "passive"))
      (node (ref "C999") (pin "2") (pinfunction "NEG_2") (pintype "passive"))
      (node (ref "CR1") (pin "2") (pinfunction "k2_2") (pintype "passive"))
      (node (ref "CR13") (pin "2") (pinfunction "k2_2") (pintype "passive"))
      (node (ref "CR3") (pin "2") (pinfunction "k2_2") (pintype "passive"))
      (node (ref "CR4") (pin "2") (pinfunction "k2_2") (pintype "passive"))
      (node (ref "CR5") (pin "2") (pinfunction "k2_2") (pintype "passive"))
      (node (ref "FL101") (pin "2") (pintype "passive"))
      (node (ref "FL102") (pin "2") (pinfunction "GND_2") (pintype "passive"))
      (node (ref "FL103") (pin "2") (pintype "passive"))
      (node (ref "FL104") (pin "2") (pinfunction "GND_2") (pintype "passive"))
      (node (ref "FL108") (pin "2") (pintype "passive"))
      (node (ref "FL109") (pin "2") (pinfunction "GND_2") (pintype "passive"))
      (node (ref "FL110") (pin "2") (pintype "passive"))
      (node (ref "FL111") (pin "2") (pinfunction "GND_2") (pintype "passive"))
      (node (ref "FL115") (pin "2") (pintype "passive"))
      (node (ref "FL116") (pin "2") (pinfunction "GND_2") (pintype "passive"))
      (node (ref "FL117") (pin "2") (pintype "passive"))
      (node (ref "FL118") (pin "2") (pinfunction "GND_2") (pintype "passive"))
      (node (ref "FL122") (pin "2") (pintype "passive"))
      (node (ref "FL123") (pin "2") (pinfunction "GND_2") (pintype "passive"))
      (node (ref "FL126") (pin "2") (pintype "passive"))
      (node (ref "FL127") (pin "2") (pinfunction "GND_2") (pintype "passive"))
      (node (ref "FL128") (pin "2") (pintype "passive"))
      (node (ref "FL129") (pin "2") (pinfunction "GND_2") (pintype "passive"))
      (node (ref "FL96") (pin "2") (pintype "passive"))
      (node (ref "FL97") (pin "2") (pinfunction "GND_2") (pintype "passive"))
      (node (ref "R15") (pin "1") (pintype "passive"))
      (node (ref "R18") (pin "2") (pintype "passive"))
      (node (ref "R189") (pin "1") (pintype "passive"))
      (node (ref "R190") (pin "2") (pintype "passive"))
      (node (ref "R25") (pin "1") (pintype "passive"))
      (node (ref "R26") (pin "1") (pintype "passive"))
      (node (ref "R261") (pin "1") (pintype "passive"))
      (node (ref "R279") (pin "2") (pintype "passive"))
      (node (ref "R281") (pin "2") (pintype "passive"))
      (node (ref "R29") (pin "1") (pintype "passive"))
      (node (ref "R328") (pin "1") (pintype "passive"))
      (node (ref "R35") (pin "2") (pintype "passive"))
      (node (ref "R36") (pin "2") (pintype "passive"))
      (node (ref "R383") (pin "1") (pintype "passive"))
      (node (ref "R383") (pin "2") (pintype "passive"))
      (node (ref "R384") (pin "1") (pintype "passive"))
      (node (ref "R384") (pin "2") (pintype "passive"))
      (node (ref "R41") (pin "2") (pintype "passive"))
      (node (ref "R43") (pin "2") (pintype "passive"))
      (node (ref "R47") (pin "1") (pintype "passive"))
      (node (ref "R48") (pin "1") (pintype "passive"))
      (node (ref "R675") (pin "1") (pintype "passive"))
      (node (ref "R677") (pin "2") (pintype "passive"))
      (node (ref "R679") (pin "2") (pintype "passive"))
      (node (ref "R681") (pin "1") (pintype "passive"))
      (node (ref "U30") (pin "11") (pinfunction "AGND_11") (pintype "passive"))
      (node (ref "U30") (pin "16") (pinfunction "DGND_16") (pintype "passive"))
      (node (ref "U30") (pin "17") (pinfunction "AGND_17") (pintype "passive"))
      (node (ref "U30") (pin "33") (pinfunction "GND_33") (pintype "passive"))
      (node (ref "U38") (pin "11") (pinfunction "AGND_11") (pintype "passive"))
      (node (ref "U38") (pin "16") (pinfunction "DGND_16") (pintype "passive"))
      (node (ref "U38") (pin "17") (pinfunction "AGND_17") (pintype "passive"))
      (node (ref "U38") (pin "33") (pinfunction "GND_33") (pintype "passive"))
      (node (ref "U64") (pin "11") (pinfunction "AGND_11") (pintype "passive"))
      (node (ref "U64") (pin "16") (pinfunction "DGND_16") (pintype "passive"))
      (node (ref "U64") (pin "17") (pinfunction "AGND_17") (pintype "passive"))
      (node (ref "U64") (pin "33") (pinfunction "GND_33") (pintype "passive"))
      (node (ref "U77") (pin "11") (pinfunction "AGND_11") (pintype "passive"))
      (node (ref "U77") (pin "16") (pinfunction "DGND_16") (pintype "passive"))
      (node (ref "U77") (pin "17") (pinfunction "AGND_17") (pintype "passive"))
      (node (ref "U77") (pin "33") (pinfunction "GND_33") (pintype "passive"))
      (node (ref "U78") (pin "11") (pinfunction "AGND_11") (pintype "passive"))
      (node (ref "U78") (pin "16") (pinfunction "DGND_16") (pintype "passive"))
      (node (ref "U78") (pin "17") (pinfunction "AGND_17") (pintype "passive"))
      (node (ref "U78") (pin "33") (pinfunction "GND_33") (pintype "passive"))
    )
    (net (code "31") (name "Net-(C67-POS)") (class "Default")
      (node (ref "C67") (pin "1") (pinfunction "POS_1") (pintype "passive"))
      (node (ref "R19") (pin "1") (pintype "passive"))
      (node (ref "U64") (pin "29") (pinfunction "LDOCC_29") (pintype "passive"))
    )
    (net (code "32") (name "Net-(C82-POS)") (class "Default")
      (node (ref "C82") (pin "1") (pinfunction "POS_1") (pintype "passive"))
      (node (ref "U64") (pin "3") (pinfunction "VDIG_3") (pintype "passive"))
    )
    (net (code "33") (name "Net-(C91-Pad1)") (class "Default")
      (node (ref "C91") (pin "1") (pintype "passive"))
      (node (ref "FL122") (pin "3") (pintype "passive"))
      (node (ref "L260") (pin "1") (pinfunction "1_1") (pintype "passive"))
    )
    (net (code "34") (name "Net-(C95-Pad1)") (class "Default")
      (node (ref "C95") (pin "1") (pintype "passive"))
      (node (ref "FL126") (pin "3") (pintype "passive"))
      (node (ref "L264") (pin "1") (pinfunction "1_1") (pintype "passive"))
    )
    (net (code "35") (name "Net-(C870-Pad1)") (class "Default")
      (node (ref "C870") (pin "1") (pintype "passive"))
      (node (ref "C97") (pin "1") (pintype "passive"))
      (node (ref "FL128") (pin "3") (pintype "passive"))
      (node (ref "L259") (pin "1") (pinfunction "1_1") (pintype "passive"))
      (node (ref "R186") (pin "1") (pintype "passive"))
    )
    (net (code "36") (name "Net-(C981-POS)") (class "Default")
      (node (ref "C981") (pin "1") (pinfunction "POS_1") (pintype "passive"))
      (node (ref "R678") (pin "1") (pintype "passive"))
      (node (ref "U38") (pin "29") (pinfunction "LDOCC_29") (pintype "passive"))
    )
    (net (code "37") (name "Net-(C987-POS)") (class "Default")
      (node (ref "C987") (pin "1") (pinfunction "POS_1") (pintype "passive"))
      (node (ref "U38") (pin "3") (pinfunction "VDIG_3") (pintype "passive"))
    )
    (net (code "38") (name "Net-(C998-POS)") (class "Default")
      (node (ref "C998") (pin "1") (pinfunction "POS_1") (pintype "passive"))
      (node (ref "R38") (pin "1") (pintype "passive"))
      (node (ref "U77") (pin "29") (pinfunction "LDOCC_29") (pintype "passive"))
    )
    (net (code "39") (name "Net-(C999-POS)") (class "Default")
      (node (ref "C999") (pin "1") (pinfunction "POS_1") (pintype "passive"))
      (node (ref "R39") (pin "1") (pintype "passive"))
      (node (ref "U78") (pin "29") (pinfunction "LDOCC_29") (pintype "passive"))
    )
    (net (code "40") (name "Net-(C1003-Pad1)") (class "Default")
      (node (ref "C1003") (pin "1") (pintype "passive"))
      (node (ref "C86") (pin "1") (pintype "passive"))
      (node (ref "C997") (pin "1") (pintype "passive"))
      (node (ref "FL117") (pin "3") (pintype "passive"))
      (node (ref "L261") (pin "1") (pinfunction "1_1") (pintype "passive"))
      (node (ref "R188") (pin "1") (pintype "passive"))
    )
    (net (code "41") (name "Net-(C1012-POS)") (class "Default")
      (node (ref "C1012") (pin "1") (pinfunction "POS_1") (pintype "passive"))
      (node (ref "R191") (pin "1") (pintype "passive"))
      (node (ref "U30") (pin "29") (pinfunction "LDOCC_29") (pintype "passive"))
    )
    (net (code "42") (name "Net-(C1013-POS)") (class "Default")
      (node (ref "C1013") (pin "1") (pinfunction "POS_1") (pintype "passive"))
      (node (ref "U77") (pin "3") (pinfunction "VDIG_3") (pintype "passive"))
    )
    (net (code "43") (name "Net-(C1014-POS)") (class "Default")
      (node (ref "C1014") (pin "1") (pinfunction "POS_1") (pintype "passive"))
      (node (ref "U78") (pin "3") (pinfunction "VDIG_3") (pintype "passive"))
    )
    (net (code "44") (name "Net-(C1024-POS)") (class "Default")
      (node (ref "C1024") (pin "1") (pinfunction "POS_1") (pintype "passive"))
      (node (ref "U30") (pin "3") (pinfunction "VDIG_3") (pintype "passive"))
    )
    (net (code "45") (name "Net-(CR1-a1)") (class "Default")
      (node (ref "C993") (pin "2") (pintype "passive"))
      (node (ref "CR1") (pin "1") (pinfunction "a1_1") (pintype "passive"))
      (node (ref "U38") (pin "19") (pinfunction "VNEGIN_19") (pintype "passive"))
    )
    (net (code "46") (name "Net-(CR1-k1,a2)") (class "Default")
      (node (ref "C989") (pin "2") (pintype "passive"))
      (node (ref "CR1") (pin "3") (pinfunction "k1,a2_3") (pintype "passive"))
    )
    (net (code "47") (name "Net-(CR3-a1)") (class "Default")
      (node (ref "C89") (pin "2") (pintype "passive"))
      (node (ref "CR3") (pin "1") (pinfunction "a1_1") (pintype "passive"))
      (node (ref "U64") (pin "19") (pinfunction "VNEGIN_19") (pintype "passive"))
    )
    (net (code "48") (name "Net-(CR3-k1,a2)") (class "Default")
      (node (ref "C88") (pin "2") (pintype "passive"))
      (node (ref "CR3") (pin "3") (pinfunction "k1,a2_3") (pintype "passive"))
    )
    (net (code "49") (name "Net-(CR4-a1)") (class "Default")
      (node (ref "C1022") (pin "2") (pintype "passive"))
      (node (ref "CR4") (pin "1") (pinfunction "a1_1") (pintype "passive"))
      (node (ref "U77") (pin "19") (pinfunction "VNEGIN_19") (pintype "passive"))
    )
    (net (code "50") (name "Net-(CR4-k1,a2)") (class "Default")
      (node (ref "C1019") (pin "2") (pintype "passive"))
      (node (ref "CR4") (pin "3") (pinfunction "k1,a2_3") (pintype "passive"))
    )
    (net (code "51") (name "Net-(CR5-a1)") (class "Default")
      (node (ref "C1023") (pin "2") (pintype "passive"))
      (node (ref "CR5") (pin "1") (pinfunction "a1_1") (pintype "passive"))
      (node (ref "U78") (pin "19") (pinfunction "VNEGIN_19") (pintype "passive"))
    )
    (net (code "52") (name "Net-(CR5-k1,a2)") (class "Default")
      (node (ref "C1020") (pin "2") (pintype "passive"))
      (node (ref "CR5") (pin "3") (pinfunction "k1,a2_3") (pintype "passive"))
    )
    (net (code "53") (name "Net-(CR13-a1)") (class "Default")
      (node (ref "C1028") (pin "2") (pintype "passive"))
      (node (ref "CR13") (pin "1") (pinfunction "a1_1") (pintype "passive"))
      (node (ref "U30") (pin "19") (pinfunction "VNEGIN_19") (pintype "passive"))
    )
    (net (code "54") (name "Net-(CR13-k1,a2)") (class "Default")
      (node (ref "C1027") (pin "2") (pintype "passive"))
      (node (ref "CR13") (pin "3") (pinfunction "k1,a2_3") (pintype "passive"))
    )
    (net (code "55") (name "Net-(FL97-OUT)") (class "Default")
      (node (ref "C64") (pin "1") (pintype "passive"))
      (node (ref "FL96") (pin "1") (pintype "passive"))
      (node (ref "FL97") (pin "3") (pinfunction "OUT_3") (pintype "passive"))
    )
    (net (code "56") (name "Net-(FL102-OUT)") (class "Default")
      (node (ref "C69") (pin "1") (pintype "passive"))
      (node (ref "FL101") (pin "1") (pintype "passive"))
      (node (ref "FL102") (pin "3") (pinfunction "OUT_3") (pintype "passive"))
    )
    (net (code "57") (name "Net-(FL104-OUT)") (class "Default")
      (node (ref "C71") (pin "1") (pintype "passive"))
      (node (ref "FL104") (pin "3") (pinfunction "OUT_3") (pintype "passive"))
      (node (ref "Q1") (pin "2") (pinfunction "COLLECTOR_2") (pintype "passive"))
      (node (ref "R24") (pin "1") (pintype "passive"))
    )
    (net (code "58") (name "Net-(FL109-OUT)") (class "Default")
      (node (ref "C76") (pin "1") (pintype "passive"))
      (node (ref "FL108") (pin "1") (pintype "passive"))
      (node (ref "FL109") (pin "3") (pinfunction "OUT_3") (pintype "passive"))
    )
    (net (code "59") (name "Net-(FL111-OUT)") (class "Default")
      (node (ref "C78") (pin "1") (pintype "passive"))
      (node (ref "FL110") (pin "1") (pintype "passive"))
      (node (ref "FL111") (pin "3") (pinfunction "OUT_3") (pintype "passive"))
    )
    (net (code "60") (name "Net-(FL116-OUT)") (class "Default")
      (node (ref "C83") (pin "1") (pintype "passive"))
      (node (ref "FL115") (pin "1") (pintype "passive"))
      (node (ref "FL116") (pin "3") (pinfunction "OUT_3") (pintype "passive"))
    )
    (net (code "61") (name "Net-(FL118-OUT)") (class "Default")
      (node (ref "C85") (pin "1") (pintype "passive"))
      (node (ref "FL117") (pin "1") (pintype "passive"))
      (node (ref "FL118") (pin "3") (pinfunction "OUT_3") (pintype "passive"))
    )
    (net (code "62") (name "Net-(FL123-OUT)") (class "Default")
      (node (ref "C90") (pin "1") (pintype "passive"))
      (node (ref "FL122") (pin "1") (pintype "passive"))
      (node (ref "FL123") (pin "3") (pinfunction "OUT_3") (pintype "passive"))
    )
    (net (code "63") (name "Net-(FL127-OUT)") (class "Default")
      (node (ref "C94") (pin "1") (pintype "passive"))
      (node (ref "FL126") (pin "1") (pintype "passive"))
      (node (ref "FL127") (pin "3") (pinfunction "OUT_3") (pintype "passive"))
    )
    (net (code "64") (name "Net-(FL129-OUT)") (class "Default")
      (node (ref "C96") (pin "1") (pintype "passive"))
      (node (ref "FL128") (pin "1") (pintype "passive"))
      (node (ref "FL129") (pin "3") (pinfunction "OUT_3") (pintype "passive"))
    )
    (net (code "65") (name "Net-(L262-Pad1)") (class "Default")
      (node (ref "L262") (pin "1") (pinfunction "1_1") (pintype "passive"))
      (node (ref "TP4") (pin "1") (pinfunction "1_1") (pintype "passive"))
      (node (ref "U64") (pin "22") (pinfunction "VDRAIN_22") (pintype "passive"))
      (node (ref "U64") (pin "23") (pinfunction "VDRAIN_23") (pintype "passive"))
    )
    (net (code "66") (name "Net-(L263-Pad1)") (class "Default")
      (node (ref "L263") (pin "1") (pinfunction "1_1") (pintype "passive"))
      (node (ref "TP49") (pin "1") (pinfunction "1_1") (pintype "passive"))
      (node (ref "U30") (pin "22") (pinfunction "VDRAIN_22") (pintype "passive"))
      (node (ref "U30") (pin "23") (pinfunction "VDRAIN_23") (pintype "passive"))
    )
    (net (code "67") (name "Net-(Q1-BASE)") (class "Default")
      (node (ref "C100") (pin "2") (pintype "passive"))
      (node (ref "Q1") (pin "1") (pinfunction "BASE_1") (pintype "passive"))
      (node (ref "R24") (pin "2") (pintype "passive"))
      (node (ref "R328") (pin "2") (pintype "passive"))
    )
    (net (code "68") (name "Net-(Q1-EMITTER)") (class "Default")
      (node (ref "FL103") (pin "1") (pintype "passive"))
      (node (ref "Q1") (pin "3") (pinfunction "EMITTER_3") (pintype "passive"))
      (node (ref "TP6") (pin "1") (pinfunction "1_1") (pintype "passive"))
    )
    (net (code "69") (name "Net-(R21-Pad2)") (class "Default")
      (node (ref "R21") (pin "2") (pintype "passive"))
      (node (ref "R279") (pin "1") (pintype "passive"))
      (node (ref "R383") (pin "3") (pintype "passive"))
    )
    (net (code "70") (name "Net-(R260-Pad2)") (class "Default")
      (node (ref "R260") (pin "2") (pintype "passive"))
      (node (ref "R281") (pin "1") (pintype "passive"))
      (node (ref "R384") (pin "3") (pintype "passive"))
    )
    (net (code "71") (name "Net-(U30-ALMH)") (class "Default")
      (node (ref "R190") (pin "1") (pintype "passive"))
      (node (ref "U30") (pin "26") (pinfunction "ALML_26") (pintype "passive"))
      (node (ref "U30") (pin "27") (pinfunction "ALMM_27") (pintype "passive"))
      (node (ref "U30") (pin "28") (pinfunction "ALMH_28") (pintype "passive"))
    )
    (net (code "72") (name "Net-(U30-CPOUT)") (class "Default")
      (node (ref "C1027") (pin "1") (pintype "passive"))
      (node (ref "U30") (pin "15") (pinfunction "CPOUT_15") (pintype "passive"))
    )
    (net (code "73") (name "Net-(U30-FIXBIAS)") (class "Default")
      (node (ref "R261") (pin "2") (pintype "passive"))
      (node (ref "U30") (pin "12") (pinfunction "FIXBIAS_12") (pintype "passive"))
    )
    (net (code "74") (name "Net-(U30-ISENSE)") (class "Default")
      (node (ref "C1009") (pin "1") (pintype "passive"))
      (node (ref "R260") (pin "1") (pintype "passive"))
      (node (ref "U30") (pin "25") (pinfunction "ISENSE_25") (pintype "passive"))
    )
    (net (code "75") (name "Net-(U30-LDOFB)") (class "Default")
      (node (ref "R189") (pin "2") (pintype "passive"))
      (node (ref "R191") (pin "2") (pintype "passive"))
      (node (ref "U30") (pin "30") (pinfunction "LDOFB_30") (pintype "passive"))
    )
    (net (code "76") (name "Net-(U30-VREF)") (class "Default")
      (node (ref "C1032") (pin "2") (pintype "passive"))
      (node (ref "U30") (pin "13") (pinfunction "VREF_13") (pintype "passive"))
    )
    (net (code "77") (name "Net-(U38-ALMH)") (class "Default")
      (node (ref "R677") (pin "1") (pintype "passive"))
      (node (ref "U38") (pin "26") (pinfunction "ALML_26") (pintype "passive"))
      (node (ref "U38") (pin "27") (pinfunction "ALMM_27") (pintype "passive"))
      (node (ref "U38") (pin "28") (pinfunction "ALMH_28") (pintype "passive"))
    )
    (net (code "78") (name "Net-(U38-CPOUT)") (class "Default")
      (node (ref "C989") (pin "1") (pintype "passive"))
      (node (ref "U38") (pin "15") (pinfunction "CPOUT_15") (pintype "passive"))
    )
    (net (code "79") (name "Net-(U38-FIXBIAS)") (class "Default")
      (node (ref "R681") (pin "2") (pintype "passive"))
      (node (ref "U38") (pin "12") (pinfunction "FIXBIAS_12") (pintype "passive"))
    )
    (net (code "80") (name "Net-(U38-ISENSE)") (class "Default")
      (node (ref "C982") (pin "1") (pintype "passive"))
      (node (ref "R679") (pin "1") (pintype "passive"))
      (node (ref "U38") (pin "25") (pinfunction "ISENSE_25") (pintype "passive"))
    )
    (net (code "81") (name "Net-(U38-LDOFB)") (class "Default")
      (node (ref "R675") (pin "2") (pintype "passive"))
      (node (ref "R678") (pin "2") (pintype "passive"))
      (node (ref "U38") (pin "30") (pinfunction "LDOFB_30") (pintype "passive"))
    )
    (net (code "82") (name "Net-(U38-VGATE)") (class "Default")
      (node (ref "NT1") (pin "3") (pinfunction "3_3") (pintype "passive"))
      (node (ref "U38") (pin "21") (pinfunction "VGATE_21") (pintype "passive"))
    )
    (net (code "83") (name "Net-(U38-VREF)") (class "Default")
      (node (ref "C992") (pin "2") (pintype "passive"))
      (node (ref "U38") (pin "13") (pinfunction "VREF_13") (pintype "passive"))
    )
    (net (code "84") (name "Net-(U64-ALMH)") (class "Default")
      (node (ref "R18") (pin "1") (pintype "passive"))
      (node (ref "U64") (pin "26") (pinfunction "ALML_26") (pintype "passive"))
      (node (ref "U64") (pin "27") (pinfunction "ALMM_27") (pintype "passive"))
      (node (ref "U64") (pin "28") (pinfunction "ALMH_28") (pintype "passive"))
    )
    (net (code "85") (name "Net-(U64-CPOUT)") (class "Default")
      (node (ref "C88") (pin "1") (pintype "passive"))
      (node (ref "U64") (pin "15") (pinfunction "CPOUT_15") (pintype "passive"))
    )
    (net (code "86") (name "Net-(U64-FIXBIAS)") (class "Default")
      (node (ref "R25") (pin "2") (pintype "passive"))
      (node (ref "U64") (pin "12") (pinfunction "FIXBIAS_12") (pintype "passive"))
    )
    (net (code "87") (name "Net-(U64-ISENSE)") (class "Default")
      (node (ref "C66") (pin "1") (pintype "passive"))
      (node (ref "R21") (pin "1") (pintype "passive"))
      (node (ref "U64") (pin "25") (pinfunction "ISENSE_25") (pintype "passive"))
    )
    (net (code "88") (name "Net-(U64-LDOFB)") (class "Default")
      (node (ref "R15") (pin "2") (pintype "passive"))
      (node (ref "R19") (pin "2") (pintype "passive"))
      (node (ref "U64") (pin "30") (pinfunction "LDOFB_30") (pintype "passive"))
    )
    (net (code "89") (name "Net-(U64-VREF)") (class "Default")
      (node (ref "C994") (pin "2") (pintype "passive"))
      (node (ref "U64") (pin "13") (pinfunction "VREF_13") (pintype "passive"))
    )
    (net (code "90") (name "Net-(U77-ALMH)") (class "Default")
      (node (ref "R35") (pin "1") (pintype "passive"))
      (node (ref "U77") (pin "26") (pinfunction "ALML_26") (pintype "passive"))
      (node (ref "U77") (pin "27") (pinfunction "ALMM_27") (pintype "passive"))
      (node (ref "U77") (pin "28") (pinfunction "ALMH_28") (pintype "passive"))
    )
    (net (code "91") (name "Net-(U77-CPOUT)") (class "Default")
      (node (ref "C1019") (pin "1") (pintype "passive"))
      (node (ref "U77") (pin "15") (pinfunction "CPOUT_15") (pintype "passive"))
    )
    (net (code "92") (name "Net-(U77-FIXBIAS)") (class "Default")
      (node (ref "R47") (pin "2") (pintype "passive"))
      (node (ref "U77") (pin "12") (pinfunction "FIXBIAS_12") (pintype "passive"))
    )
    (net (code "93") (name "Net-(U77-ISENSE)") (class "Default")
      (node (ref "C995") (pin "1") (pintype "passive"))
      (node (ref "R41") (pin "1") (pintype "passive"))
      (node (ref "U77") (pin "25") (pinfunction "ISENSE_25") (pintype "passive"))
    )
    (net (code "94") (name "Net-(U77-LDOFB)") (class "Default")
      (node (ref "R26") (pin "2") (pintype "passive"))
      (node (ref "R38") (pin "2") (pintype "passive"))
      (node (ref "U77") (pin "30") (pinfunction "LDOFB_30") (pintype "passive"))
    )
    (net (code "95") (name "Net-(U77-VGATE)") (class "Default")
      (node (ref "NT3") (pin "3") (pinfunction "3_3") (pintype "passive"))
      (node (ref "U77") (pin "21") (pinfunction "VGATE_21") (pintype "passive"))
    )
    (net (code "96") (name "Net-(U77-VREF)") (class "Default")
      (node (ref "C1029") (pin "2") (pintype "passive"))
      (node (ref "U77") (pin "13") (pinfunction "VREF_13") (pintype "passive"))
    )
    (net (code "97") (name "Net-(U78-ALMH)") (class "Default")
      (node (ref "R36") (pin "1") (pintype "passive"))
      (node (ref "U78") (pin "26") (pinfunction "ALML_26") (pintype "passive"))
      (node (ref "U78") (pin "27") (pinfunction "ALMM_27") (pintype "passive"))
      (node (ref "U78") (pin "28") (pinfunction "ALMH_28") (pintype "passive"))
    )
    (net (code "98") (name "Net-(U78-CPOUT)") (class "Default")
      (node (ref "C1020") (pin "1") (pintype "passive"))
      (node (ref "U78") (pin "15") (pinfunction "CPOUT_15") (pintype "passive"))
    )
    (net (code "99") (name "Net-(U78-FIXBIAS)") (class "Default")
      (node (ref "R48") (pin "2") (pintype "passive"))
      (node (ref "U78") (pin "12") (pinfunction "FIXBIAS_12") (pintype "passive"))
    )
    (net (code "100") (name "Net-(U78-ISENSE)") (class "Default")
      (node (ref "C996") (pin "1") (pintype "passive"))
      (node (ref "R43") (pin "1") (pintype "passive"))
      (node (ref "U78") (pin "25") (pinfunction "ISENSE_25") (pintype "passive"))
    )
    (net (code "101") (name "Net-(U78-LDOFB)") (class "Default")
      (node (ref "R29") (pin "2") (pintype "passive"))
      (node (ref "R39") (pin "2") (pintype "passive"))
      (node (ref "U78") (pin "30") (pinfunction "LDOFB_30") (pintype "passive"))
    )
    (net (code "102") (name "Net-(U78-VREF)") (class "Default")
      (node (ref "C1031") (pin "2") (pintype "passive"))
      (node (ref "U78") (pin "13") (pinfunction "VREF_13") (pintype "passive"))
    )
    (net (code "103") (name "unconnected-(U30-ALMSET-Pad10)") (class "Default")
      (node (ref "U30") (pin "10") (pinfunction "ALMSET_10") (pintype "passive"))
    )
    (net (code "104") (name "unconnected-(U30-ALMTRG-Pad9)") (class "Default")
      (node (ref "U30") (pin "9") (pinfunction "ALMTRG_9") (pintype "passive"))
    )
    (net (code "105") (name "unconnected-(U30-BGCAP-Pad6)") (class "Default")
      (node (ref "U30") (pin "6") (pinfunction "BGCAP_6") (pintype "passive"))
    )
    (net (code "106") (name "unconnected-(U30-CURALM-Pad8)") (class "Default")
      (node (ref "U30") (pin "8") (pinfunction "CURALM_8") (pintype "passive"))
    )
    (net (code "107") (name "unconnected-(U30-EN-Pad7)") (class "Default")
      (node (ref "U30") (pin "7") (pinfunction "EN_7") (pintype "passive"))
    )
    (net (code "108") (name "unconnected-(U30-PORCAP-Pad5)") (class "Default")
      (node (ref "U30") (pin "5") (pinfunction "PORCAP_5") (pintype "passive"))
    )
    (net (code "109") (name "unconnected-(U30-TRGOUT-Pad24)") (class "Default")
      (node (ref "U30") (pin "24") (pinfunction "TRGOUT_24") (pintype "passive"))
    )
    (net (code "110") (name "unconnected-(U30-VDDALM-Pad31)") (class "Default")
      (node (ref "U30") (pin "31") (pinfunction "VDDALM_31") (pintype "passive"))
    )
    (net (code "111") (name "unconnected-(U30-VDDCHK-Pad32)") (class "Default")
      (node (ref "U30") (pin "32") (pinfunction "VDDCHK_32") (pintype "passive"))
    )
    (net (code "112") (name "unconnected-(U30-VDIGFB-Pad4)") (class "Default")
      (node (ref "U30") (pin "4") (pinfunction "VDIGFB_4") (pintype "passive"))
    )
    (net (code "113") (name "unconnected-(U30-VGATEFB-Pad20)") (class "Default")
      (node (ref "U30") (pin "20") (pinfunction "VGATEFB_20") (pintype "passive"))
    )
    (net (code "114") (name "unconnected-(U30-VNEGFB-Pad18)") (class "Default")
      (node (ref "U30") (pin "18") (pinfunction "VNEGFB_18") (pintype "passive"))
    )
    (net (code "115") (name "unconnected-(U38-ALMSET-Pad10)") (class "Default")
      (node (ref "U38") (pin "10") (pinfunction "ALMSET_10") (pintype "passive"))
    )
    (net (code "116") (name "unconnected-(U38-ALMTRG-Pad9)") (class "Default")
      (node (ref "U38") (pin "9") (pinfunction "ALMTRG_9") (pintype "passive"))
    )
    (net (code "117") (name "unconnected-(U38-BGCAP-Pad6)") (class "Default")
      (node (ref "U38") (pin "6") (pinfunction "BGCAP_6") (pintype "passive"))
    )
    (net (code "118") (name "unconnected-(U38-CURALM-Pad8)") (class "Default")
      (node (ref "U38") (pin "8") (pinfunction "CURALM_8") (pintype "passive"))
    )
    (net (code "119") (name "unconnected-(U38-EN-Pad7)") (class "Default")
      (node (ref "U38") (pin "7") (pinfunction "EN_7") (pintype "passive"))
    )
    (net (code "120") (name "unconnected-(U38-PORCAP-Pad5)") (class "Default")
      (node (ref "U38") (pin "5") (pinfunction "PORCAP_5") (pintype "passive"))
    )
    (net (code "121") (name "unconnected-(U38-TRGOUT-Pad24)") (class "Default")
      (node (ref "U38") (pin "24") (pinfunction "TRGOUT_24") (pintype "passive"))
    )
    (net (code "122") (name "unconnected-(U38-VDDALM-Pad31)") (class "Default")
      (node (ref "U38") (pin "31") (pinfunction "VDDALM_31") (pintype "passive"))
    )
    (net (code "123") (name "unconnected-(U38-VDDCHK-Pad32)") (class "Default")
      (node (ref "U38") (pin "32") (pinfunction "VDDCHK_32") (pintype "passive"))
    )
    (net (code "124") (name "unconnected-(U38-VDIGFB-Pad4)") (class "Default")
      (node (ref "U38") (pin "4") (pinfunction "VDIGFB_4") (pintype "passive"))
    )
    (net (code "125") (name "unconnected-(U38-VGATEFB-Pad20)") (class "Default")
      (node (ref "U38") (pin "20") (pinfunction "VGATEFB_20") (pintype "passive"))
    )
    (net (code "126") (name "unconnected-(U38-VNEGFB-Pad18)") (class "Default")
      (node (ref "U38") (pin "18") (pinfunction "VNEGFB_18") (pintype "passive"))
    )
    (net (code "127") (name "unconnected-(U64-ALMSET-Pad10)") (class "Default")
      (node (ref "U64") (pin "10") (pinfunction "ALMSET_10") (pintype "passive"))
    )
    (net (code "128") (name "unconnected-(U64-ALMTRG-Pad9)") (class "Default")
      (node (ref "U64") (pin "9") (pinfunction "ALMTRG_9") (pintype "passive"))
    )
    (net (code "129") (name "unconnected-(U64-BGCAP-Pad6)") (class "Default")
      (node (ref "U64") (pin "6") (pinfunction "BGCAP_6") (pintype "passive"))
    )
    (net (code "130") (name "unconnected-(U64-CURALM-Pad8)") (class "Default")
      (node (ref "U64") (pin "8") (pinfunction "CURALM_8") (pintype "passive"))
    )
    (net (code "131") (name "unconnected-(U64-EN-Pad7)") (class "Default")
      (node (ref "U64") (pin "7") (pinfunction "EN_7") (pintype "passive"))
    )
    (net (code "132") (name "unconnected-(U64-PORCAP-Pad5)") (class "Default")
      (node (ref "U64") (pin "5") (pinfunction "PORCAP_5") (pintype "passive"))
    )
    (net (code "133") (name "unconnected-(U64-TRGOUT-Pad24)") (class "Default")
      (node (ref "U64") (pin "24") (pinfunction "TRGOUT_24") (pintype "passive"))
    )
    (net (code "134") (name "unconnected-(U64-VDDALM-Pad31)") (class "Default")
      (node (ref "U64") (pin "31") (pinfunction "VDDALM_31") (pintype "passive"))
    )
    (net (code "135") (name "unconnected-(U64-VDDCHK-Pad32)") (class "Default")
      (node (ref "U64") (pin "32") (pinfunction "VDDCHK_32") (pintype "passive"))
    )
    (net (code "136") (name "unconnected-(U64-VDIGFB-Pad4)") (class "Default")
      (node (ref "U64") (pin "4") (pinfunction "VDIGFB_4") (pintype "passive"))
    )
    (net (code "137") (name "unconnected-(U64-VGATEFB-Pad20)") (class "Default")
      (node (ref "U64") (pin "20") (pinfunction "VGATEFB_20") (pintype "passive"))
    )
    (net (code "138") (name "unconnected-(U64-VNEGFB-Pad18)") (class "Default")
      (node (ref "U64") (pin "18") (pinfunction "VNEGFB_18") (pintype "passive"))
    )
    (net (code "139") (name "unconnected-(U77-ALMSET-Pad10)") (class "Default")
      (node (ref "U77") (pin "10") (pinfunction "ALMSET_10") (pintype "passive"))
    )
    (net (code "140") (name "unconnected-(U77-ALMTRG-Pad9)") (class "Default")
      (node (ref "U77") (pin "9") (pinfunction "ALMTRG_9") (pintype "passive"))
    )
    (net (code "141") (name "unconnected-(U77-BGCAP-Pad6)") (class "Default")
      (node (ref "U77") (pin "6") (pinfunction "BGCAP_6") (pintype "passive"))
    )
    (net (code "142") (name "unconnected-(U77-CURALM-Pad8)") (class "Default")
      (node (ref "U77") (pin "8") (pinfunction "CURALM_8") (pintype "passive"))
    )
    (net (code "143") (name "unconnected-(U77-EN-Pad7)") (class "Default")
      (node (ref "U77") (pin "7") (pinfunction "EN_7") (pintype "passive"))
    )
    (net (code "144") (name "unconnected-(U77-PORCAP-Pad5)") (class "Default")
      (node (ref "U77") (pin "5") (pinfunction "PORCAP_5") (pintype "passive"))
    )
    (net (code "145") (name "unconnected-(U77-TRGOUT-Pad24)") (class "Default")
      (node (ref "U77") (pin "24") (pinfunction "TRGOUT_24") (pintype "passive"))
    )
    (net (code "146") (name "unconnected-(U77-VDDALM-Pad31)") (class "Default")
      (node (ref "U77") (pin "31") (pinfunction "VDDALM_31") (pintype "passive"))
    )
    (net (code "147") (name "unconnected-(U77-VDDCHK-Pad32)") (class "Default")
      (node (ref "U77") (pin "32") (pinfunction "VDDCHK_32") (pintype "passive"))
    )
    (net (code "148") (name "unconnected-(U77-VDIGFB-Pad4)") (class "Default")
      (node (ref "U77") (pin "4") (pinfunction "VDIGFB_4") (pintype "passive"))
    )
    (net (code "149") (name "unconnected-(U77-VGATEFB-Pad20)") (class "Default")
      (node (ref "U77") (pin "20") (pinfunction "VGATEFB_20") (pintype "passive"))
    )
    (net (code "150") (name "unconnected-(U77-VNEGFB-Pad18)") (class "Default")
      (node (ref "U77") (pin "18") (pinfunction "VNEGFB_18") (pintype "passive"))
    )
    (net (code "151") (name "unconnected-(U78-ALMSET-Pad10)") (class "Default")
      (node (ref "U78") (pin "10") (pinfunction "ALMSET_10") (pintype "passive"))
    )
    (net (code "152") (name "unconnected-(U78-ALMTRG-Pad9)") (class "Default")
      (node (ref "U78") (pin "9") (pinfunction "ALMTRG_9") (pintype "passive"))
    )
    (net (code "153") (name "unconnected-(U78-BGCAP-Pad6)") (class "Default")
      (node (ref "U78") (pin "6") (pinfunction "BGCAP_6") (pintype "passive"))
    )
    (net (code "154") (name "unconnected-(U78-CURALM-Pad8)") (class "Default")
      (node (ref "U78") (pin "8") (pinfunction "CURALM_8") (pintype "passive"))
    )
    (net (code "155") (name "unconnected-(U78-EN-Pad7)") (class "Default")
      (node (ref "U78") (pin "7") (pinfunction "EN_7") (pintype "passive"))
    )
    (net (code "156") (name "unconnected-(U78-PORCAP-Pad5)") (class "Default")
      (node (ref "U78") (pin "5") (pinfunction "PORCAP_5") (pintype "passive"))
    )
    (net (code "157") (name "unconnected-(U78-TRGOUT-Pad24)") (class "Default")
      (node (ref "U78") (pin "24") (pinfunction "TRGOUT_24") (pintype "passive"))
    )
    (net (code "158") (name "unconnected-(U78-VDDALM-Pad31)") (class "Default")
      (node (ref "U78") (pin "31") (pinfunction "VDDALM_31") (pintype "passive"))
    )
    (net (code "159") (name "unconnected-(U78-VDDCHK-Pad32)") (class "Default")
      (node (ref "U78") (pin "32") (pinfunction "VDDCHK_32") (pintype "passive"))
    )
    (net (code "160") (name "unconnected-(U78-VDIGFB-Pad4)") (class "Default")
      (node (ref "U78") (pin "4") (pinfunction "VDIGFB_4") (pintype "passive"))
    )
    (net (code "161") (name "unconnected-(U78-VGATEFB-Pad20)") (class "Default")
      (node (ref "U78") (pin "20") (pinfunction "VGATEFB_20") (pintype "passive"))
    )
    (net (code "162") (name "unconnected-(U78-VNEGFB-Pad18)") (class "Default")
      (node (ref "U78") (pin "18") (pinfunction "VNEGFB_18") (pintype "passive"))
    )
  )
)
